# MAIN.net
KiCad netlist of a schematic drawn in Altium Designer
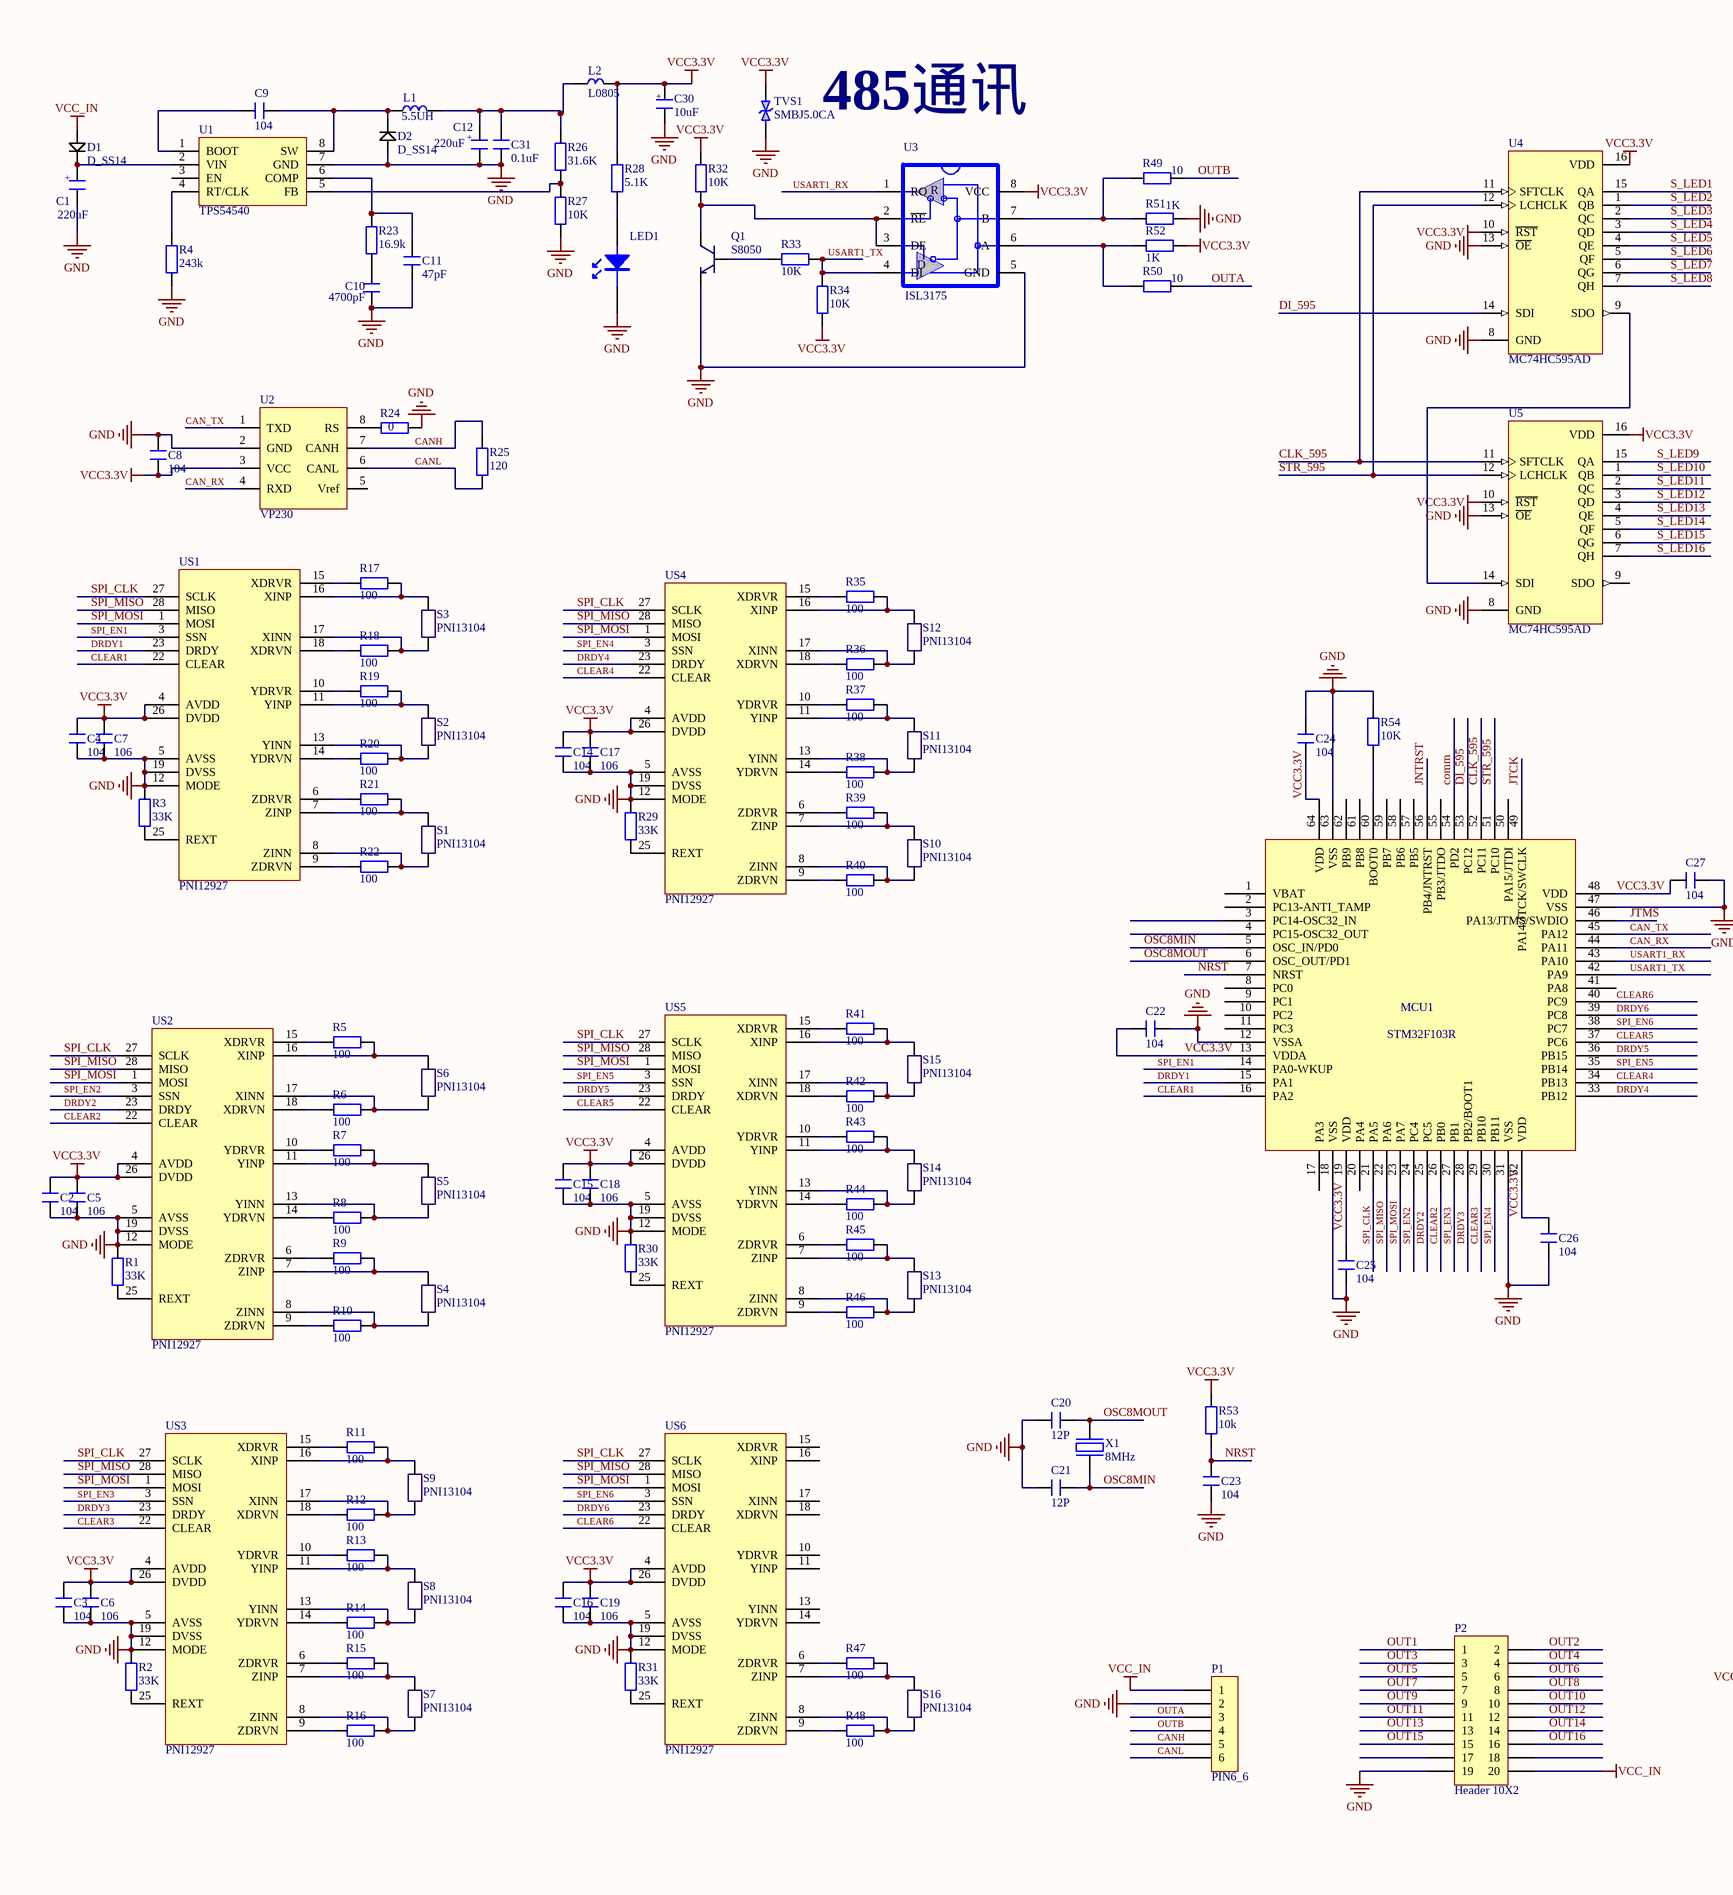
[diagram p0: MAIN.SchDoc, left]
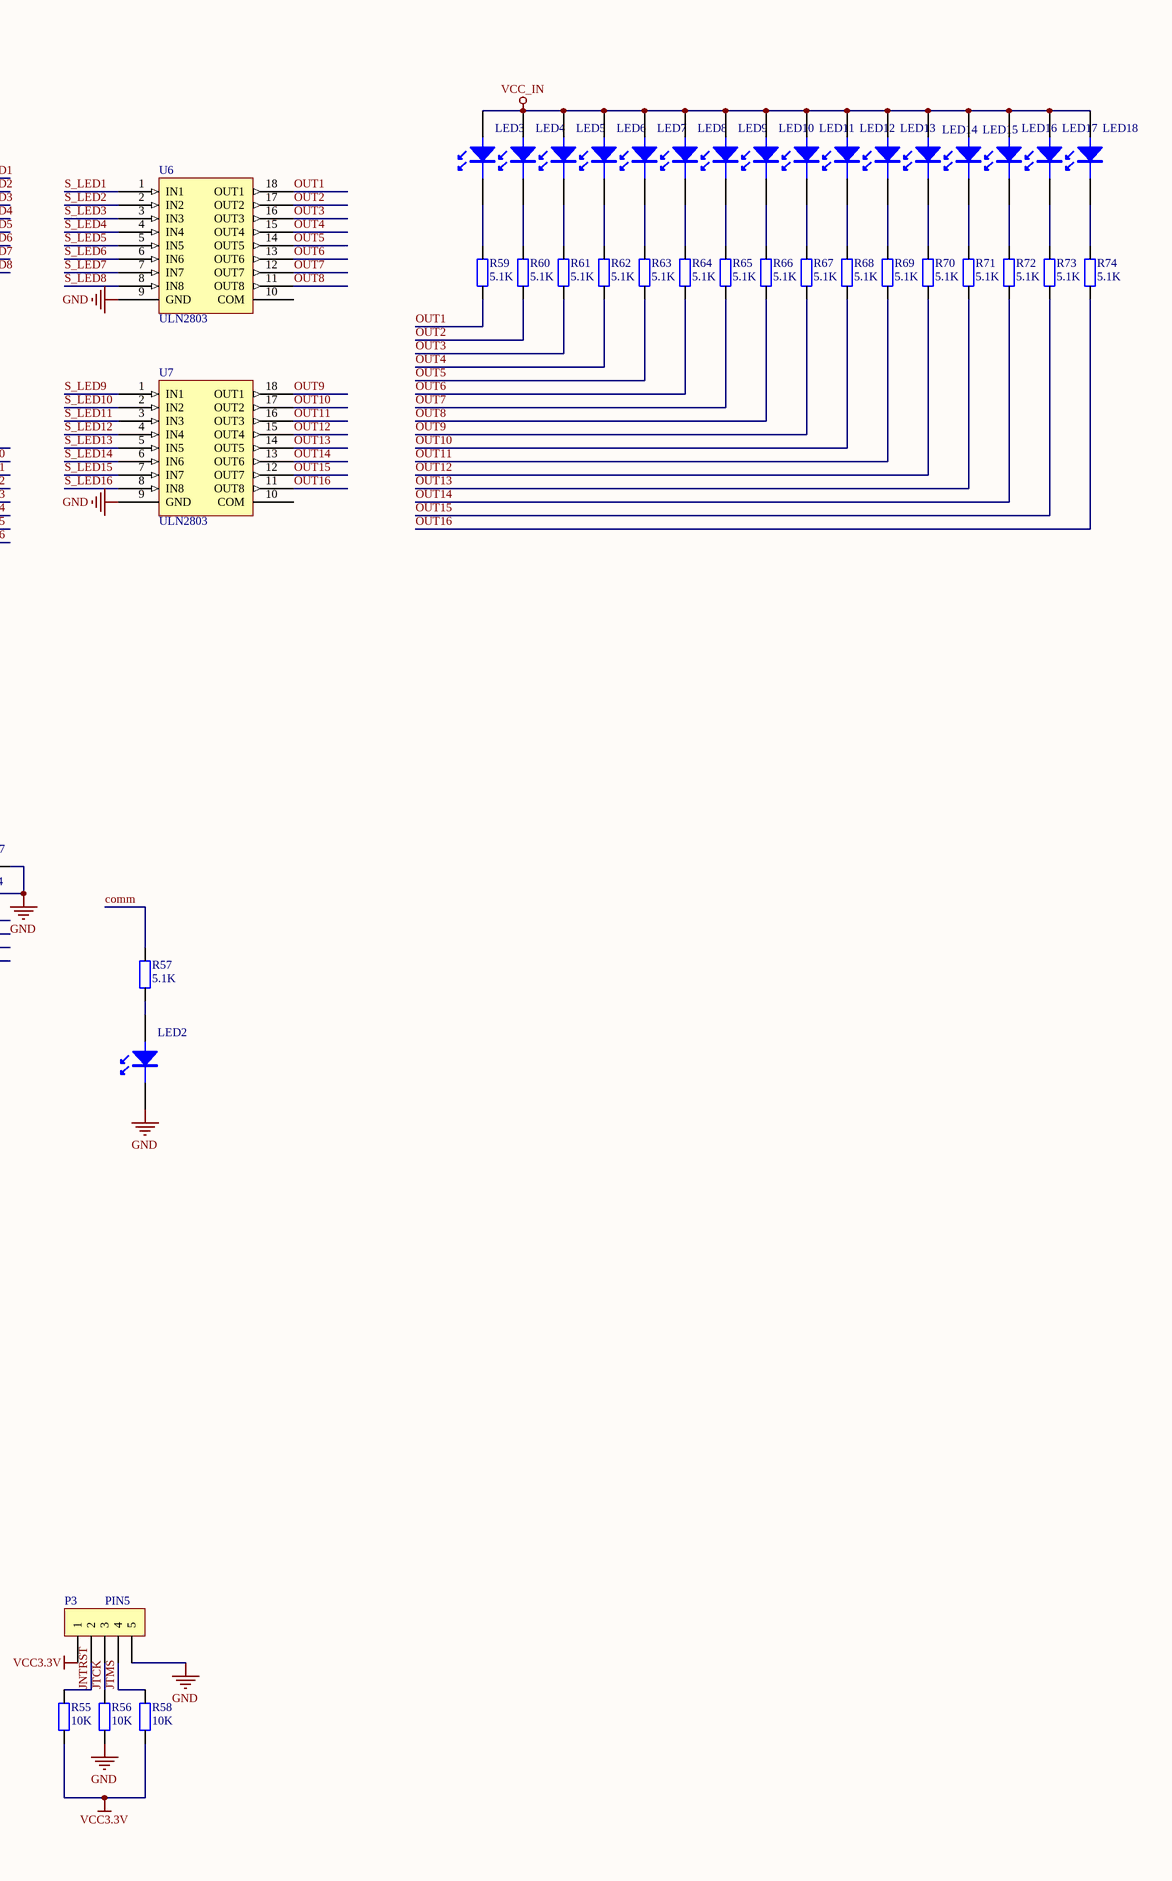
[diagram p1: MAIN.SchDoc, right]

(export (version "E")
  (design (tool "Eeschema 10.0.6"))
  (components
    (comp (ref "C1")
      (value "220uF")
      (footprint "自编封装库:CAP_SMT_1")
      (libsource (lib "自编原件库") (part "CAP_SMT_1"))
    )
    (comp (ref "C2") (value "104") (footprint "自编封装库:C0603") (libsource (lib "自编原件库") (part "CAP_SMT_0603")))
    (comp (ref "C3") (value "104") (footprint "自编封装库:C0603") (libsource (lib "自编原件库") (part "CAP_SMT_0603")))
    (comp (ref "C4") (value "104") (footprint "自编封装库:C0603") (libsource (lib "自编原件库") (part "CAP_SMT_0603")))
    (comp (ref "C5") (value "106") (footprint "自编封装库:C0805") (libsource (lib "自编原件库") (part "CAP_SMT_0805")))
    (comp (ref "C6") (value "106") (footprint "自编封装库:C0805") (libsource (lib "自编原件库") (part "CAP_SMT_0805")))
    (comp (ref "C7") (value "106") (footprint "自编封装库:C0805") (libsource (lib "自编原件库") (part "CAP_SMT_0805")))
    (comp (ref "C8") (value "104") (footprint "自编封装库:C0603") (libsource (lib "自编原件库") (part "CAP_SMT_0603")))
    (comp (ref "C9") (value "104") (footprint "自编封装库:C0603") (libsource (lib "自编原件库") (part "CAP_SMT_0603")))
    (comp (ref "C10")
      (value "4700pF")
      (footprint "自编封装库:C0603")
      (libsource (lib "自编原件库") (part "CAP_SMT_0603"))
    )
    (comp (ref "C11")
      (value "47pF")
      (footprint "自编封装库:C0603")
      (libsource (lib "自编原件库") (part "CAP_SMT_0603"))
    )
    (comp (ref "C12")
      (value "220uF")
      (footprint "自编封装库:CAP_SMT_1")
      (libsource (lib "自编原件库") (part "CAP_SMT_1"))
    )
    (comp (ref "C14") (value "104") (footprint "自编封装库:C0603") (libsource (lib "自编原件库") (part "CAP_SMT_0603")))
    (comp (ref "C15") (value "104") (footprint "自编封装库:C0603") (libsource (lib "自编原件库") (part "CAP_SMT_0603")))
    (comp (ref "C16") (value "104") (footprint "自编封装库:C0603") (libsource (lib "自编原件库") (part "CAP_SMT_0603")))
    (comp (ref "C17") (value "106") (footprint "自编封装库:C0805") (libsource (lib "自编原件库") (part "CAP_SMT_0805")))
    (comp (ref "C18") (value "106") (footprint "自编封装库:C0805") (libsource (lib "自编原件库") (part "CAP_SMT_0805")))
    (comp (ref "C19") (value "106") (footprint "自编封装库:C0805") (libsource (lib "自编原件库") (part "CAP_SMT_0805")))
    (comp (ref "C20") (value "12P") (footprint "自编封装库:C0603") (libsource (lib "自编原件库") (part "CAP_SMT_0603")))
    (comp (ref "C21") (value "12P") (footprint "自编封装库:C0603") (libsource (lib "自编原件库") (part "CAP_SMT_0603")))
    (comp (ref "C22") (value "104") (footprint "自编封装库:C0603") (libsource (lib "自编原件库") (part "CAP_SMT_0603")))
    (comp (ref "C23") (value "104") (footprint "自编封装库:C0603") (libsource (lib "自编原件库") (part "CAP_SMT_0603")))
    (comp (ref "C24") (value "104") (footprint "自编封装库:C0603") (libsource (lib "自编原件库") (part "CAP_SMT_0603")))
    (comp (ref "C25") (value "104") (footprint "自编封装库:C0603") (libsource (lib "自编原件库") (part "CAP_SMT_0603")))
    (comp (ref "C26") (value "104") (footprint "自编封装库:C0603") (libsource (lib "自编原件库") (part "CAP_SMT_0603")))
    (comp (ref "C27") (value "104") (footprint "自编封装库:C0603") (libsource (lib "自编原件库") (part "CAP_SMT_0603")))
    (comp (ref "C30")
      (value "10uF")
      (footprint "自编封装库:C1206")
      (libsource (lib "自编原件库") (part "CAP_SMT_1206"))
    )
    (comp (ref "C31")
      (value "0.1uF")
      (footprint "自编封装库:C0603")
      (libsource (lib "自编原件库") (part "CAP_SMT_0603"))
    )
    (comp (ref "D1") (value "D_SS14") (footprint "自编封装库:D_3.0*5.0") (libsource (lib "自编原件库") (part "D_SS14")))
    (comp (ref "D2") (value "D_SS14") (footprint "自编封装库:D_3.0*5.0") (libsource (lib "自编原件库") (part "D_SS14")))
    (comp (ref "L1") (value "5.5UH") (footprint "自编封装库:L7*7") (libsource (lib "自编原件库") (part "L_SMT_7*7*4")))
    (comp (ref "L2") (value "L0805") (footprint "自编封装库:L0805") (libsource (lib "自编原件库") (part "L_SMT_0805")))
    (comp (ref "LED1") (value "~") (footprint "LED1-AK") (libsource (lib "*") (part "LED")))
    (comp (ref "LED2") (value "~") (footprint "LED1-AK") (libsource (lib "*") (part "LED")))
    (comp (ref "LED3") (value "~") (footprint "LED1-AK") (libsource (lib "*") (part "LED")))
    (comp (ref "LED4") (value "~") (footprint "LED1-AK") (libsource (lib "*") (part "LED")))
    (comp (ref "LED5") (value "~") (footprint "LED1-AK") (libsource (lib "*") (part "LED")))
    (comp (ref "LED6") (value "~") (footprint "LED1-AK") (libsource (lib "*") (part "LED")))
    (comp (ref "LED7") (value "~") (footprint "LED1-AK") (libsource (lib "*") (part "LED")))
    (comp (ref "LED8") (value "~") (footprint "LED1-AK") (libsource (lib "*") (part "LED")))
    (comp (ref "LED9") (value "~") (footprint "LED1-AK") (libsource (lib "*") (part "LED")))
    (comp (ref "LED10") (value "~") (footprint "LED1-AK") (libsource (lib "*") (part "LED")))
    (comp (ref "LED11") (value "~") (footprint "LED1-AK") (libsource (lib "*") (part "LED")))
    (comp (ref "LED12") (value "~") (footprint "LED1-AK") (libsource (lib "*") (part "LED")))
    (comp (ref "LED13") (value "~") (footprint "LED1-AK") (libsource (lib "*") (part "LED")))
    (comp (ref "LED14") (value "~") (footprint "LED1-AK") (libsource (lib "*") (part "LED")))
    (comp (ref "LED15") (value "~") (footprint "LED1-AK") (libsource (lib "*") (part "LED")))
    (comp (ref "LED16") (value "~") (footprint "LED1-AK") (libsource (lib "*") (part "LED")))
    (comp (ref "LED17") (value "~") (footprint "LED1-AK") (libsource (lib "*") (part "LED")))
    (comp (ref "LED18") (value "~") (footprint "LED1-AK") (libsource (lib "*") (part "LED")))
    (comp (ref "MCU1")
      (value "STM32F103R")
      (footprint "TQFP64_STM32")
      (libsource (lib "自编原件库") (part "STM32F103RXX_64"))
    )
    (comp (ref "P1")
      (value "PIN6_6")
      (footprint "自编封装库:KF350W_6")
      (libsource (lib "自编原件库") (part "PIN6_6*1_3.81MM"))
    )
    (comp (ref "P2")
      (value "Header 10X2")
      (footprint "PIN20_10*2_2.54MM_1")
      (description "Header, 10-Pin, Dual row")
      (fields (field (name "PUBLISHER") "Altium Limited"))
      (libsource (lib "Miscellaneous Connectors") (part "Header 10X2"))
    )
    (comp (ref "P3")
      (value "PIN5")
      (footprint "自编封装库:PIN5_5*1_2.54MM_2")
      (libsource (lib "自编原件库") (part "PIN5_5*1_2.54mm"))
    )
    (comp (ref "Q1") (value "S8050") (footprint "自编封装库:SOT-23") (libsource (lib "自编原件库") (part "QS8050")))
    (comp (ref "R1") (value "33K") (footprint "R0603") (libsource (lib "自编原件库") (part "RES_SMT_0603")))
    (comp (ref "R2") (value "33K") (footprint "R0603") (libsource (lib "自编原件库") (part "RES_SMT_0603")))
    (comp (ref "R3") (value "33K") (footprint "R0603") (libsource (lib "自编原件库") (part "RES_SMT_0603")))
    (comp (ref "R4") (value "243k") (footprint "R0603") (libsource (lib "自编原件库") (part "RES_SMT_0603")))
    (comp (ref "R5") (value "100") (footprint "R0603") (libsource (lib "自编原件库") (part "RES_SMT_0603")))
    (comp (ref "R6") (value "100") (footprint "R0603") (libsource (lib "自编原件库") (part "RES_SMT_0603")))
    (comp (ref "R7") (value "100") (footprint "R0603") (libsource (lib "自编原件库") (part "RES_SMT_0603")))
    (comp (ref "R8") (value "100") (footprint "R0603") (libsource (lib "自编原件库") (part "RES_SMT_0603")))
    (comp (ref "R9") (value "100") (footprint "R0603") (libsource (lib "自编原件库") (part "RES_SMT_0603")))
    (comp (ref "R10") (value "100") (footprint "R0603") (libsource (lib "自编原件库") (part "RES_SMT_0603")))
    (comp (ref "R11") (value "100") (footprint "R0603") (libsource (lib "自编原件库") (part "RES_SMT_0603")))
    (comp (ref "R12") (value "100") (footprint "R0603") (libsource (lib "自编原件库") (part "RES_SMT_0603")))
    (comp (ref "R13") (value "100") (footprint "R0603") (libsource (lib "自编原件库") (part "RES_SMT_0603")))
    (comp (ref "R14") (value "100") (footprint "R0603") (libsource (lib "自编原件库") (part "RES_SMT_0603")))
    (comp (ref "R15") (value "100") (footprint "R0603") (libsource (lib "自编原件库") (part "RES_SMT_0603")))
    (comp (ref "R16") (value "100") (footprint "R0603") (libsource (lib "自编原件库") (part "RES_SMT_0603")))
    (comp (ref "R17") (value "100") (footprint "R0603") (libsource (lib "自编原件库") (part "RES_SMT_0603")))
    (comp (ref "R18") (value "100") (footprint "R0603") (libsource (lib "自编原件库") (part "RES_SMT_0603")))
    (comp (ref "R19") (value "100") (footprint "R0603") (libsource (lib "自编原件库") (part "RES_SMT_0603")))
    (comp (ref "R20") (value "100") (footprint "R0603") (libsource (lib "自编原件库") (part "RES_SMT_0603")))
    (comp (ref "R21") (value "100") (footprint "R0603") (libsource (lib "自编原件库") (part "RES_SMT_0603")))
    (comp (ref "R22") (value "100") (footprint "R0603") (libsource (lib "自编原件库") (part "RES_SMT_0603")))
    (comp (ref "R23") (value "16.9k") (footprint "R0603") (libsource (lib "自编原件库") (part "RES_SMT_0603")))
    (comp (ref "R24") (value "0") (footprint "R0603") (libsource (lib "自编原件库") (part "RES_SMT_0603")))
    (comp (ref "R25") (value "120") (footprint "R0603") (libsource (lib "自编原件库") (part "RES_SMT_0603")))
    (comp (ref "R26") (value "31.6K") (footprint "R0603") (libsource (lib "自编原件库") (part "RES_SMT_0603")))
    (comp (ref "R27") (value "10K") (footprint "R0603") (libsource (lib "自编原件库") (part "RES_SMT_0603")))
    (comp (ref "R28") (value "5.1K") (footprint "R0603") (libsource (lib "自编原件库") (part "RES_SMT_0603")))
    (comp (ref "R29") (value "33K") (footprint "R0603") (libsource (lib "自编原件库") (part "RES_SMT_0603")))
    (comp (ref "R30") (value "33K") (footprint "R0603") (libsource (lib "自编原件库") (part "RES_SMT_0603")))
    (comp (ref "R31") (value "33K") (footprint "R0603") (libsource (lib "自编原件库") (part "RES_SMT_0603")))
    (comp (ref "R32") (value "10K") (footprint "R0603") (libsource (lib "自编原件库") (part "RES_SMT_0603")))
    (comp (ref "R33") (value "10K") (footprint "R0603") (libsource (lib "自编原件库") (part "RES_SMT_0603")))
    (comp (ref "R34") (value "10K") (footprint "R0603") (libsource (lib "自编原件库") (part "RES_SMT_0603")))
    (comp (ref "R35") (value "100") (footprint "R0603") (libsource (lib "自编原件库") (part "RES_SMT_0603")))
    (comp (ref "R36") (value "100") (footprint "R0603") (libsource (lib "自编原件库") (part "RES_SMT_0603")))
    (comp (ref "R37") (value "100") (footprint "R0603") (libsource (lib "自编原件库") (part "RES_SMT_0603")))
    (comp (ref "R38") (value "100") (footprint "R0603") (libsource (lib "自编原件库") (part "RES_SMT_0603")))
    (comp (ref "R39") (value "100") (footprint "R0603") (libsource (lib "自编原件库") (part "RES_SMT_0603")))
    (comp (ref "R40") (value "100") (footprint "R0603") (libsource (lib "自编原件库") (part "RES_SMT_0603")))
    (comp (ref "R41") (value "100") (footprint "R0603") (libsource (lib "自编原件库") (part "RES_SMT_0603")))
    (comp (ref "R42") (value "100") (footprint "R0603") (libsource (lib "自编原件库") (part "RES_SMT_0603")))
    (comp (ref "R43") (value "100") (footprint "R0603") (libsource (lib "自编原件库") (part "RES_SMT_0603")))
    (comp (ref "R44") (value "100") (footprint "R0603") (libsource (lib "自编原件库") (part "RES_SMT_0603")))
    (comp (ref "R45") (value "100") (footprint "R0603") (libsource (lib "自编原件库") (part "RES_SMT_0603")))
    (comp (ref "R46") (value "100") (footprint "R0603") (libsource (lib "自编原件库") (part "RES_SMT_0603")))
    (comp (ref "R47") (value "100") (footprint "R0603") (libsource (lib "自编原件库") (part "RES_SMT_0603")))
    (comp (ref "R48") (value "100") (footprint "R0603") (libsource (lib "自编原件库") (part "RES_SMT_0603")))
    (comp (ref "R49") (value "10") (footprint "R0603") (libsource (lib "自编原件库") (part "RES_SMT_0603")))
    (comp (ref "R50") (value "10") (footprint "R0603") (libsource (lib "自编原件库") (part "RES_SMT_0603")))
    (comp (ref "R51") (value "1K") (footprint "R0603") (libsource (lib "自编原件库") (part "RES_SMT_0603")))
    (comp (ref "R52") (value "1K") (footprint "R0603") (libsource (lib "自编原件库") (part "RES_SMT_0603")))
    (comp (ref "R53") (value "10k") (footprint "R0603") (libsource (lib "自编原件库") (part "RES_SMT_0603")))
    (comp (ref "R54") (value "10K") (footprint "R0603") (libsource (lib "自编原件库") (part "RES_SMT_0603")))
    (comp (ref "R55") (value "10K") (footprint "R0603") (libsource (lib "自编原件库") (part "RES_SMT_0603")))
    (comp (ref "R56") (value "10K") (footprint "R0603") (libsource (lib "自编原件库") (part "RES_SMT_0603")))
    (comp (ref "R57") (value "5.1K") (footprint "R0603") (libsource (lib "自编原件库") (part "RES_SMT_0603")))
    (comp (ref "R58") (value "10K") (footprint "R0603") (libsource (lib "自编原件库") (part "RES_SMT_0603")))
    (comp (ref "R59") (value "5.1K") (footprint "R0603") (libsource (lib "自编原件库") (part "RES_SMT_0603")))
    (comp (ref "R60") (value "5.1K") (footprint "R0603") (libsource (lib "自编原件库") (part "RES_SMT_0603")))
    (comp (ref "R61") (value "5.1K") (footprint "R0603") (libsource (lib "自编原件库") (part "RES_SMT_0603")))
    (comp (ref "R62") (value "5.1K") (footprint "R0603") (libsource (lib "自编原件库") (part "RES_SMT_0603")))
    (comp (ref "R63") (value "5.1K") (footprint "R0603") (libsource (lib "自编原件库") (part "RES_SMT_0603")))
    (comp (ref "R64") (value "5.1K") (footprint "R0603") (libsource (lib "自编原件库") (part "RES_SMT_0603")))
    (comp (ref "R65") (value "5.1K") (footprint "R0603") (libsource (lib "自编原件库") (part "RES_SMT_0603")))
    (comp (ref "R66") (value "5.1K") (footprint "R0603") (libsource (lib "自编原件库") (part "RES_SMT_0603")))
    (comp (ref "R67") (value "5.1K") (footprint "R0603") (libsource (lib "自编原件库") (part "RES_SMT_0603")))
    (comp (ref "R68") (value "5.1K") (footprint "R0603") (libsource (lib "自编原件库") (part "RES_SMT_0603")))
    (comp (ref "R69") (value "5.1K") (footprint "R0603") (libsource (lib "自编原件库") (part "RES_SMT_0603")))
    (comp (ref "R70") (value "5.1K") (footprint "R0603") (libsource (lib "自编原件库") (part "RES_SMT_0603")))
    (comp (ref "R71") (value "5.1K") (footprint "R0603") (libsource (lib "自编原件库") (part "RES_SMT_0603")))
    (comp (ref "R72") (value "5.1K") (footprint "R0603") (libsource (lib "自编原件库") (part "RES_SMT_0603")))
    (comp (ref "R73") (value "5.1K") (footprint "R0603") (libsource (lib "自编原件库") (part "RES_SMT_0603")))
    (comp (ref "R74") (value "5.1K") (footprint "R0603") (libsource (lib "自编原件库") (part "RES_SMT_0603")))
    (comp (ref "S1")
      (value "PNI13104")
      (footprint "自编封装库:PNI-13104")
      (libsource (lib "自编原件库") (part "PNI13104"))
    )
    (comp (ref "S2")
      (value "PNI13104")
      (footprint "自编封装库:PNI-13104")
      (libsource (lib "自编原件库") (part "PNI13104"))
    )
    (comp (ref "S3")
      (value "PNI13104")
      (footprint "自编封装库:PNI-13104")
      (libsource (lib "自编原件库") (part "PNI13104"))
    )
    (comp (ref "S4")
      (value "PNI13104")
      (footprint "自编封装库:PNI-13104")
      (libsource (lib "自编原件库") (part "PNI13104"))
    )
    (comp (ref "S5")
      (value "PNI13104")
      (footprint "自编封装库:PNI-13104")
      (libsource (lib "自编原件库") (part "PNI13104"))
    )
    (comp (ref "S6")
      (value "PNI13104")
      (footprint "自编封装库:PNI-13104")
      (libsource (lib "自编原件库") (part "PNI13104"))
    )
    (comp (ref "S7")
      (value "PNI13104")
      (footprint "自编封装库:PNI-13104")
      (libsource (lib "自编原件库") (part "PNI13104"))
    )
    (comp (ref "S8")
      (value "PNI13104")
      (footprint "自编封装库:PNI-13104")
      (libsource (lib "自编原件库") (part "PNI13104"))
    )
    (comp (ref "S9")
      (value "PNI13104")
      (footprint "自编封装库:PNI-13104")
      (libsource (lib "自编原件库") (part "PNI13104"))
    )
    (comp (ref "S10")
      (value "PNI13104")
      (footprint "自编封装库:PNI-13104")
      (libsource (lib "自编原件库") (part "PNI13104"))
    )
    (comp (ref "S11")
      (value "PNI13104")
      (footprint "自编封装库:PNI-13104")
      (libsource (lib "自编原件库") (part "PNI13104"))
    )
    (comp (ref "S12")
      (value "PNI13104")
      (footprint "自编封装库:PNI-13104")
      (libsource (lib "自编原件库") (part "PNI13104"))
    )
    (comp (ref "S13")
      (value "PNI13104")
      (footprint "自编封装库:PNI-13104")
      (libsource (lib "自编原件库") (part "PNI13104"))
    )
    (comp (ref "S14")
      (value "PNI13104")
      (footprint "自编封装库:PNI-13104")
      (libsource (lib "自编原件库") (part "PNI13104"))
    )
    (comp (ref "S15")
      (value "PNI13104")
      (footprint "自编封装库:PNI-13104")
      (libsource (lib "自编原件库") (part "PNI13104"))
    )
    (comp (ref "S16")
      (value "PNI13104")
      (footprint "自编封装库:PNI-13104")
      (libsource (lib "自编原件库") (part "PNI13104"))
    )
    (comp (ref "TVS1")
      (value "SMBJ5.0CA")
      (footprint "SMBJ6.5CA")
      (description "片式瞬态抑制二极管")
      (libsource (lib "自编原件库") (part "TVS"))
    )
    (comp (ref "U1")
      (value "TPS54540")
      (footprint "自编封装库:SOP8_1")
      (libsource (lib "自编原件库") (part "TPS54540"))
    )
    (comp (ref "U2") (value "VP230") (footprint "自编封装库:SOP8") (libsource (lib "自编原件库") (part "VP230")))
    (comp (ref "U3") (value "ISL3175") (footprint "SO-8") (libsource (lib "*") (part "MAX485")))
    (comp (ref "U4")
      (value "MC74HC595AD")
      (footprint "自编封装库:SOP16")
      (description "8-Bit Serial-Input/Serial or Prallel-Output Shift Register with Latched 3-State Outputs")
      (fields (field (name "PUBLISHER") "Altium Limited"))
      (libsource (lib "ON Semi Logic Register") (part "MC74HC595AD"))
    )
    (comp (ref "U5")
      (value "MC74HC595AD")
      (footprint "sop16")
      (description "8-Bit Serial-Input/Serial or Prallel-Output Shift Register with Latched 3-State Outputs")
      (fields (field (name "PUBLISHER") "Altium Limited"))
      (libsource (lib "ON Semi Logic Register") (part "MC74HC595AD"))
    )
    (comp (ref "U6") (value "ULN2803") (footprint "SO-G18") (libsource (lib "总图") (part "ULN2803")))
    (comp (ref "U7") (value "ULN2803") (footprint "SO-G18") (libsource (lib "总图") (part "ULN2803")))
    (comp (ref "US1")
      (value "PNI12927")
      (footprint "自编封装库:MLF_28")
      (libsource (lib "自编原件库") (part "PNI12927"))
    )
    (comp (ref "US2")
      (value "PNI12927")
      (footprint "自编封装库:MLF_28")
      (libsource (lib "自编原件库") (part "PNI12927"))
    )
    (comp (ref "US3")
      (value "PNI12927")
      (footprint "自编封装库:MLF_28")
      (libsource (lib "自编原件库") (part "PNI12927"))
    )
    (comp (ref "US4")
      (value "PNI12927")
      (footprint "自编封装库:MLF_28")
      (libsource (lib "自编原件库") (part "PNI12927"))
    )
    (comp (ref "US5")
      (value "PNI12927")
      (footprint "自编封装库:MLF_28")
      (libsource (lib "自编原件库") (part "PNI12927"))
    )
    (comp (ref "US6")
      (value "PNI12927")
      (footprint "自编封装库:MLF_28")
      (libsource (lib "自编原件库") (part "PNI12927"))
    )
    (comp (ref "X1")
      (value "8MHz")
      (footprint "自编封装库:XTAL_49SMD")
      (description "假贴片晶振")
      (libsource (lib "自编原件库") (part "XTAL_49SMD"))
    )
  )
  (nets
    (net (code "1") (name "/CANH") (class "Default")
      (node (ref "P1") (pin "5") (pinfunction "5_5") (pintype "passive"))
      (node (ref "R25") (pin "2") (pinfunction "2_2") (pintype "passive"))
      (node (ref "U2") (pin "7") (pinfunction "CANH_7") (pintype "passive"))
    )
    (net (code "2") (name "/CANL") (class "Default")
      (node (ref "P1") (pin "6") (pinfunction "6_6") (pintype "passive"))
      (node (ref "R25") (pin "1") (pinfunction "1_1") (pintype "passive"))
      (node (ref "U2") (pin "6") (pinfunction "CANL_6") (pintype "passive"))
    )
    (net (code "3") (name "/CAN_RX") (class "Default")
      (node (ref "MCU1") (pin "44") (pinfunction "PA11_44") (pintype "passive"))
      (node (ref "U2") (pin "4") (pinfunction "RXD_4") (pintype "passive"))
    )
    (net (code "4") (name "/CAN_TX") (class "Default")
      (node (ref "MCU1") (pin "45") (pinfunction "PA12_45") (pintype "passive"))
      (node (ref "U2") (pin "1") (pinfunction "TXD_1") (pintype "passive"))
    )
    (net (code "5") (name "/CLEAR1") (class "Default")
      (node (ref "MCU1") (pin "16") (pinfunction "PA2_16") (pintype "passive"))
      (node (ref "US1") (pin "22") (pinfunction "CLEAR_22") (pintype "passive"))
    )
    (net (code "6") (name "/CLEAR2") (class "Default")
      (node (ref "MCU1") (pin "26") (pinfunction "PB0_26") (pintype "passive"))
      (node (ref "US2") (pin "22") (pinfunction "CLEAR_22") (pintype "passive"))
    )
    (net (code "7") (name "/CLEAR3") (class "Default")
      (node (ref "MCU1") (pin "29") (pinfunction "PB10_29") (pintype "passive"))
      (node (ref "US3") (pin "22") (pinfunction "CLEAR_22") (pintype "passive"))
    )
    (net (code "8") (name "/CLEAR4") (class "Default")
      (node (ref "MCU1") (pin "34") (pinfunction "PB13_34") (pintype "passive"))
      (node (ref "US4") (pin "22") (pinfunction "CLEAR_22") (pintype "passive"))
    )
    (net (code "9") (name "/CLEAR5") (class "Default")
      (node (ref "MCU1") (pin "37") (pinfunction "PC6_37") (pintype "passive"))
      (node (ref "US5") (pin "22") (pinfunction "CLEAR_22") (pintype "passive"))
    )
    (net (code "10") (name "/CLEAR6") (class "Default")
      (node (ref "MCU1") (pin "40") (pinfunction "PC9_40") (pintype "passive"))
      (node (ref "US6") (pin "22") (pinfunction "CLEAR_22") (pintype "passive"))
    )
    (net (code "11") (name "/CLK_595") (class "Default")
      (node (ref "MCU1") (pin "52") (pinfunction "PC11_52") (pintype "passive"))
      (node (ref "U4") (pin "11") (pinfunction "SFTCLK_11") (pintype "input"))
      (node (ref "U5") (pin "11") (pinfunction "SFTCLK_11") (pintype "input"))
    )
    (net (code "12") (name "/DI_595") (class "Default")
      (node (ref "MCU1") (pin "53") (pinfunction "PC12_53") (pintype "passive"))
      (node (ref "U4") (pin "14") (pinfunction "SDI_14") (pintype "input"))
    )
    (net (code "13") (name "/DRDY1") (class "Default")
      (node (ref "MCU1") (pin "15") (pinfunction "PA1_15") (pintype "passive"))
      (node (ref "US1") (pin "23") (pinfunction "DRDY_23") (pintype "passive"))
    )
    (net (code "14") (name "/DRDY2") (class "Default")
      (node (ref "MCU1") (pin "25") (pinfunction "PC5_25") (pintype "passive"))
      (node (ref "US2") (pin "23") (pinfunction "DRDY_23") (pintype "passive"))
    )
    (net (code "15") (name "/DRDY3") (class "Default")
      (node (ref "MCU1") (pin "28") (pinfunction "PB2/BOOT1_28") (pintype "passive"))
      (node (ref "US3") (pin "23") (pinfunction "DRDY_23") (pintype "passive"))
    )
    (net (code "16") (name "/DRDY4") (class "Default")
      (node (ref "MCU1") (pin "33") (pinfunction "PB12_33") (pintype "passive"))
      (node (ref "US4") (pin "23") (pinfunction "DRDY_23") (pintype "passive"))
    )
    (net (code "17") (name "/DRDY5") (class "Default")
      (node (ref "MCU1") (pin "36") (pinfunction "PB15_36") (pintype "passive"))
      (node (ref "US5") (pin "23") (pinfunction "DRDY_23") (pintype "passive"))
    )
    (net (code "18") (name "/DRDY6") (class "Default")
      (node (ref "MCU1") (pin "39") (pinfunction "PC8_39") (pintype "passive"))
      (node (ref "US6") (pin "23") (pinfunction "DRDY_23") (pintype "passive"))
    )
    (net (code "19") (name "/JNTRST") (class "Default")
      (node (ref "MCU1") (pin "56") (pinfunction "PB4/JNTRST_56") (pintype "passive"))
      (node (ref "P3") (pin "2") (pinfunction "2_2") (pintype "passive"))
      (node (ref "R55") (pin "2") (pinfunction "2_2") (pintype "passive"))
    )
    (net (code "20") (name "/JTCK") (class "Default")
      (node (ref "MCU1") (pin "49") (pinfunction "PA14/JTCK/SWCLK_49") (pintype "passive"))
      (node (ref "P3") (pin "3") (pinfunction "3_3") (pintype "passive"))
      (node (ref "R56") (pin "2") (pinfunction "2_2") (pintype "passive"))
    )
    (net (code "21") (name "/JTMS") (class "Default")
      (node (ref "MCU1") (pin "46") (pinfunction "PA13/JTMS/SWDIO_46") (pintype "passive"))
      (node (ref "P3") (pin "4") (pinfunction "4_4") (pintype "passive"))
      (node (ref "R58") (pin "2") (pinfunction "2_2") (pintype "passive"))
    )
    (net (code "22") (name "/NRST") (class "Default")
      (node (ref "C23") (pin "2") (pinfunction "2_2") (pintype "passive"))
      (node (ref "MCU1") (pin "7") (pinfunction "NRST_7") (pintype "passive"))
      (node (ref "R53") (pin "1") (pinfunction "1_1") (pintype "passive"))
    )
    (net (code "23") (name "/OSC8MIN") (class "Default")
      (node (ref "C21") (pin "2") (pinfunction "2_2") (pintype "passive"))
      (node (ref "MCU1") (pin "5") (pinfunction "OSC_IN/PD0_5") (pintype "passive"))
      (node (ref "X1") (pin "1") (pinfunction "1_1") (pintype "passive"))
    )
    (net (code "24") (name "/OSC8MOUT") (class "Default")
      (node (ref "C20") (pin "2") (pinfunction "2_2") (pintype "passive"))
      (node (ref "MCU1") (pin "6") (pinfunction "OSC_OUT/PD1_6") (pintype "passive"))
      (node (ref "X1") (pin "2") (pinfunction "2_2") (pintype "passive"))
    )
    (net (code "25") (name "/OUT1") (class "Default")
      (node (ref "P2") (pin "1") (pinfunction "1_1") (pintype "passive"))
      (node (ref "R59") (pin "1") (pinfunction "1_1") (pintype "passive"))
      (node (ref "U6") (pin "18") (pinfunction "OUT1_18") (pintype "output"))
    )
    (net (code "26") (name "/OUT2") (class "Default")
      (node (ref "P2") (pin "2") (pinfunction "2_2") (pintype "passive"))
      (node (ref "R60") (pin "1") (pinfunction "1_1") (pintype "passive"))
      (node (ref "U6") (pin "17") (pinfunction "OUT2_17") (pintype "output"))
    )
    (net (code "27") (name "/OUT3") (class "Default")
      (node (ref "P2") (pin "3") (pinfunction "3_3") (pintype "passive"))
      (node (ref "R61") (pin "1") (pinfunction "1_1") (pintype "passive"))
      (node (ref "U6") (pin "16") (pinfunction "OUT3_16") (pintype "output"))
    )
    (net (code "28") (name "/OUT4") (class "Default")
      (node (ref "P2") (pin "4") (pinfunction "4_4") (pintype "passive"))
      (node (ref "R62") (pin "1") (pinfunction "1_1") (pintype "passive"))
      (node (ref "U6") (pin "15") (pinfunction "OUT4_15") (pintype "output"))
    )
    (net (code "29") (name "/OUT5") (class "Default")
      (node (ref "P2") (pin "5") (pinfunction "5_5") (pintype "passive"))
      (node (ref "R63") (pin "1") (pinfunction "1_1") (pintype "passive"))
      (node (ref "U6") (pin "14") (pinfunction "OUT5_14") (pintype "output"))
    )
    (net (code "30") (name "/OUT6") (class "Default")
      (node (ref "P2") (pin "6") (pinfunction "6_6") (pintype "passive"))
      (node (ref "R64") (pin "1") (pinfunction "1_1") (pintype "passive"))
      (node (ref "U6") (pin "13") (pinfunction "OUT6_13") (pintype "output"))
    )
    (net (code "31") (name "/OUT7") (class "Default")
      (node (ref "P2") (pin "7") (pinfunction "7_7") (pintype "passive"))
      (node (ref "R65") (pin "1") (pinfunction "1_1") (pintype "passive"))
      (node (ref "U6") (pin "12") (pinfunction "OUT7_12") (pintype "output"))
    )
    (net (code "32") (name "/OUT8") (class "Default")
      (node (ref "P2") (pin "8") (pinfunction "8_8") (pintype "passive"))
      (node (ref "R66") (pin "1") (pinfunction "1_1") (pintype "passive"))
      (node (ref "U6") (pin "11") (pinfunction "OUT8_11") (pintype "output"))
    )
    (net (code "33") (name "/OUT9") (class "Default")
      (node (ref "P2") (pin "9") (pinfunction "9_9") (pintype "passive"))
      (node (ref "R67") (pin "1") (pinfunction "1_1") (pintype "passive"))
      (node (ref "U7") (pin "18") (pinfunction "OUT1_18") (pintype "output"))
    )
    (net (code "34") (name "/OUT10") (class "Default")
      (node (ref "P2") (pin "10") (pinfunction "10_10") (pintype "passive"))
      (node (ref "R68") (pin "1") (pinfunction "1_1") (pintype "passive"))
      (node (ref "U7") (pin "17") (pinfunction "OUT2_17") (pintype "output"))
    )
    (net (code "35") (name "/OUT11") (class "Default")
      (node (ref "P2") (pin "11") (pinfunction "11_11") (pintype "passive"))
      (node (ref "R69") (pin "1") (pinfunction "1_1") (pintype "passive"))
      (node (ref "U7") (pin "16") (pinfunction "OUT3_16") (pintype "output"))
    )
    (net (code "36") (name "/OUT12") (class "Default")
      (node (ref "P2") (pin "12") (pinfunction "12_12") (pintype "passive"))
      (node (ref "R70") (pin "1") (pinfunction "1_1") (pintype "passive"))
      (node (ref "U7") (pin "15") (pinfunction "OUT4_15") (pintype "output"))
    )
    (net (code "37") (name "/OUT13") (class "Default")
      (node (ref "P2") (pin "13") (pinfunction "13_13") (pintype "passive"))
      (node (ref "R71") (pin "1") (pinfunction "1_1") (pintype "passive"))
      (node (ref "U7") (pin "14") (pinfunction "OUT5_14") (pintype "output"))
    )
    (net (code "38") (name "/OUT14") (class "Default")
      (node (ref "P2") (pin "14") (pinfunction "14_14") (pintype "passive"))
      (node (ref "R72") (pin "1") (pinfunction "1_1") (pintype "passive"))
      (node (ref "U7") (pin "13") (pinfunction "OUT6_13") (pintype "output"))
    )
    (net (code "39") (name "/OUT15") (class "Default")
      (node (ref "P2") (pin "15") (pinfunction "15_15") (pintype "passive"))
      (node (ref "R73") (pin "1") (pinfunction "1_1") (pintype "passive"))
      (node (ref "U7") (pin "12") (pinfunction "OUT7_12") (pintype "output"))
    )
    (net (code "40") (name "/OUT16") (class "Default")
      (node (ref "P2") (pin "16") (pinfunction "16_16") (pintype "passive"))
      (node (ref "R74") (pin "1") (pinfunction "1_1") (pintype "passive"))
      (node (ref "U7") (pin "11") (pinfunction "OUT8_11") (pintype "output"))
    )
    (net (code "41") (name "/OUTA") (class "Default")
      (node (ref "P1") (pin "3") (pinfunction "3_3") (pintype "passive"))
      (node (ref "R50") (pin "1") (pinfunction "1_1") (pintype "passive"))
    )
    (net (code "42") (name "/OUTB") (class "Default")
      (node (ref "P1") (pin "4") (pinfunction "4_4") (pintype "passive"))
      (node (ref "R49") (pin "1") (pinfunction "1_1") (pintype "passive"))
    )
    (net (code "43") (name "/SPI_CLK") (class "Default")
      (node (ref "MCU1") (pin "21") (pinfunction "PA5_21") (pintype "passive"))
      (node (ref "US1") (pin "27") (pinfunction "SCLK_27") (pintype "passive"))
      (node (ref "US2") (pin "27") (pinfunction "SCLK_27") (pintype "passive"))
      (node (ref "US3") (pin "27") (pinfunction "SCLK_27") (pintype "passive"))
      (node (ref "US4") (pin "27") (pinfunction "SCLK_27") (pintype "passive"))
      (node (ref "US5") (pin "27") (pinfunction "SCLK_27") (pintype "passive"))
      (node (ref "US6") (pin "27") (pinfunction "SCLK_27") (pintype "passive"))
    )
    (net (code "44") (name "/SPI_EN1") (class "Default")
      (node (ref "MCU1") (pin "14") (pinfunction "PA0-WKUP_14") (pintype "passive"))
      (node (ref "US1") (pin "3") (pinfunction "SSN_3") (pintype "passive"))
    )
    (net (code "45") (name "/SPI_EN2") (class "Default")
      (node (ref "MCU1") (pin "24") (pinfunction "PC4_24") (pintype "passive"))
      (node (ref "US2") (pin "3") (pinfunction "SSN_3") (pintype "passive"))
    )
    (net (code "46") (name "/SPI_EN3") (class "Default")
      (node (ref "MCU1") (pin "27") (pinfunction "PB1_27") (pintype "passive"))
      (node (ref "US3") (pin "3") (pinfunction "SSN_3") (pintype "passive"))
    )
    (net (code "47") (name "/SPI_EN4") (class "Default")
      (node (ref "MCU1") (pin "30") (pinfunction "PB11_30") (pintype "passive"))
      (node (ref "US4") (pin "3") (pinfunction "SSN_3") (pintype "passive"))
    )
    (net (code "48") (name "/SPI_EN5") (class "Default")
      (node (ref "MCU1") (pin "35") (pinfunction "PB14_35") (pintype "passive"))
      (node (ref "US5") (pin "3") (pinfunction "SSN_3") (pintype "passive"))
    )
    (net (code "49") (name "/SPI_EN6") (class "Default")
      (node (ref "MCU1") (pin "38") (pinfunction "PC7_38") (pintype "passive"))
      (node (ref "US6") (pin "3") (pinfunction "SSN_3") (pintype "passive"))
    )
    (net (code "50") (name "/SPI_MISO") (class "Default")
      (node (ref "MCU1") (pin "22") (pinfunction "PA6_22") (pintype "passive"))
      (node (ref "US1") (pin "28") (pinfunction "MISO_28") (pintype "passive"))
      (node (ref "US2") (pin "28") (pinfunction "MISO_28") (pintype "passive"))
      (node (ref "US3") (pin "28") (pinfunction "MISO_28") (pintype "passive"))
      (node (ref "US4") (pin "28") (pinfunction "MISO_28") (pintype "passive"))
      (node (ref "US5") (pin "28") (pinfunction "MISO_28") (pintype "passive"))
      (node (ref "US6") (pin "28") (pinfunction "MISO_28") (pintype "passive"))
    )
    (net (code "51") (name "/SPI_MOSI") (class "Default")
      (node (ref "MCU1") (pin "23") (pinfunction "PA7_23") (pintype "passive"))
      (node (ref "US1") (pin "1") (pinfunction "MOSI_1") (pintype "passive"))
      (node (ref "US2") (pin "1") (pinfunction "MOSI_1") (pintype "passive"))
      (node (ref "US3") (pin "1") (pinfunction "MOSI_1") (pintype "passive"))
      (node (ref "US4") (pin "1") (pinfunction "MOSI_1") (pintype "passive"))
      (node (ref "US5") (pin "1") (pinfunction "MOSI_1") (pintype "passive"))
      (node (ref "US6") (pin "1") (pinfunction "MOSI_1") (pintype "passive"))
    )
    (net (code "52") (name "/STR_595") (class "Default")
      (node (ref "MCU1") (pin "51") (pinfunction "PC10_51") (pintype "passive"))
      (node (ref "U4") (pin "12") (pinfunction "LCHCLK_12") (pintype "input"))
      (node (ref "U5") (pin "12") (pinfunction "LCHCLK_12") (pintype "input"))
    )
    (net (code "53") (name "/S_LED1") (class "Default")
      (node (ref "U4") (pin "15") (pinfunction "QA_15") (pintype "tri_state"))
      (node (ref "U6") (pin "1") (pinfunction "IN1_1") (pintype "input"))
    )
    (net (code "54") (name "/S_LED2") (class "Default")
      (node (ref "U4") (pin "1") (pinfunction "QB_1") (pintype "tri_state"))
      (node (ref "U6") (pin "2") (pinfunction "IN2_2") (pintype "input"))
    )
    (net (code "55") (name "/S_LED3") (class "Default")
      (node (ref "U4") (pin "2") (pinfunction "QC_2") (pintype "tri_state"))
      (node (ref "U6") (pin "3") (pinfunction "IN3_3") (pintype "input"))
    )
    (net (code "56") (name "/S_LED4") (class "Default")
      (node (ref "U4") (pin "3") (pinfunction "QD_3") (pintype "tri_state"))
      (node (ref "U6") (pin "4") (pinfunction "IN4_4") (pintype "input"))
    )
    (net (code "57") (name "/S_LED5") (class "Default")
      (node (ref "U4") (pin "4") (pinfunction "QE_4") (pintype "tri_state"))
      (node (ref "U6") (pin "5") (pinfunction "IN5_5") (pintype "input"))
    )
    (net (code "58") (name "/S_LED6") (class "Default")
      (node (ref "U4") (pin "5") (pinfunction "QF_5") (pintype "tri_state"))
      (node (ref "U6") (pin "6") (pinfunction "IN6_6") (pintype "input"))
    )
    (net (code "59") (name "/S_LED7") (class "Default")
      (node (ref "U4") (pin "6") (pinfunction "QG_6") (pintype "tri_state"))
      (node (ref "U6") (pin "7") (pinfunction "IN7_7") (pintype "input"))
    )
    (net (code "60") (name "/S_LED8") (class "Default")
      (node (ref "U4") (pin "7") (pinfunction "QH_7") (pintype "tri_state"))
      (node (ref "U6") (pin "8") (pinfunction "IN8_8") (pintype "input"))
    )
    (net (code "61") (name "/S_LED9") (class "Default")
      (node (ref "U5") (pin "15") (pinfunction "QA_15") (pintype "tri_state"))
      (node (ref "U7") (pin "1") (pinfunction "IN1_1") (pintype "input"))
    )
    (net (code "62") (name "/S_LED10") (class "Default")
      (node (ref "U5") (pin "1") (pinfunction "QB_1") (pintype "tri_state"))
      (node (ref "U7") (pin "2") (pinfunction "IN2_2") (pintype "input"))
    )
    (net (code "63") (name "/S_LED11") (class "Default")
      (node (ref "U5") (pin "2") (pinfunction "QC_2") (pintype "tri_state"))
      (node (ref "U7") (pin "3") (pinfunction "IN3_3") (pintype "input"))
    )
    (net (code "64") (name "/S_LED12") (class "Default")
      (node (ref "U5") (pin "3") (pinfunction "QD_3") (pintype "tri_state"))
      (node (ref "U7") (pin "4") (pinfunction "IN4_4") (pintype "input"))
    )
    (net (code "65") (name "/S_LED13") (class "Default")
      (node (ref "U5") (pin "4") (pinfunction "QE_4") (pintype "tri_state"))
      (node (ref "U7") (pin "5") (pinfunction "IN5_5") (pintype "input"))
    )
    (net (code "66") (name "/S_LED14") (class "Default")
      (node (ref "U5") (pin "5") (pinfunction "QF_5") (pintype "tri_state"))
      (node (ref "U7") (pin "6") (pinfunction "IN6_6") (pintype "input"))
    )
    (net (code "67") (name "/S_LED15") (class "Default")
      (node (ref "U5") (pin "6") (pinfunction "QG_6") (pintype "tri_state"))
      (node (ref "U7") (pin "7") (pinfunction "IN7_7") (pintype "input"))
    )
    (net (code "68") (name "/S_LED16") (class "Default")
      (node (ref "U5") (pin "7") (pinfunction "QH_7") (pintype "tri_state"))
      (node (ref "U7") (pin "8") (pinfunction "IN8_8") (pintype "input"))
    )
    (net (code "69") (name "/USART1_RX") (class "Default")
      (node (ref "MCU1") (pin "43") (pinfunction "PA10_43") (pintype "passive"))
      (node (ref "U3") (pin "1") (pinfunction "RO_1") (pintype "passive"))
    )
    (net (code "70") (name "/USART1_TX") (class "Default")
      (node (ref "MCU1") (pin "42") (pinfunction "PA9_42") (pintype "passive"))
      (node (ref "R33") (pin "1") (pinfunction "1_1") (pintype "passive"))
      (node (ref "R34") (pin "2") (pinfunction "2_2") (pintype "passive"))
      (node (ref "U3") (pin "4") (pinfunction "DI_4") (pintype "passive"))
    )
    (net (code "71") (name "/comm") (class "Default")
      (node (ref "MCU1") (pin "54") (pinfunction "PD2_54") (pintype "passive"))
      (node (ref "R57") (pin "2") (pinfunction "2_2") (pintype "passive"))
    )
    (net (code "72") (name "GND") (class "Default")
      (node (ref "C1") (pin "2") (pinfunction "2_2") (pintype "passive"))
      (node (ref "C10") (pin "1") (pinfunction "1_1") (pintype "passive"))
      (node (ref "C11") (pin "1") (pinfunction "1_1") (pintype "passive"))
      (node (ref "C12") (pin "2") (pinfunction "2_2") (pintype "passive"))
      (node (ref "C14") (pin "1") (pinfunction "1_1") (pintype "passive"))
      (node (ref "C15") (pin "1") (pinfunction "1_1") (pintype "passive"))
      (node (ref "C16") (pin "1") (pinfunction "1_1") (pintype "passive"))
      (node (ref "C17") (pin "1") (pinfunction "1_1") (pintype "passive"))
      (node (ref "C18") (pin "1") (pinfunction "1_1") (pintype "passive"))
      (node (ref "C19") (pin "1") (pinfunction "1_1") (pintype "passive"))
      (node (ref "C2") (pin "1") (pinfunction "1_1") (pintype "passive"))
      (node (ref "C20") (pin "1") (pinfunction "1_1") (pintype "passive"))
      (node (ref "C21") (pin "1") (pinfunction "1_1") (pintype "passive"))
      (node (ref "C22") (pin "2") (pinfunction "2_2") (pintype "passive"))
      (node (ref "C23") (pin "1") (pinfunction "1_1") (pintype "passive"))
      (node (ref "C24") (pin "2") (pinfunction "2_2") (pintype "passive"))
      (node (ref "C25") (pin "1") (pinfunction "1_1") (pintype "passive"))
      (node (ref "C26") (pin "1") (pinfunction "1_1") (pintype "passive"))
      (node (ref "C27") (pin "2") (pinfunction "2_2") (pintype "passive"))
      (node (ref "C3") (pin "1") (pinfunction "1_1") (pintype "passive"))
      (node (ref "C30") (pin "2") (pinfunction "2_2") (pintype "passive"))
      (node (ref "C31") (pin "1") (pinfunction "1_1") (pintype "passive"))
      (node (ref "C4") (pin "1") (pinfunction "1_1") (pintype "passive"))
      (node (ref "C5") (pin "1") (pinfunction "1_1") (pintype "passive"))
      (node (ref "C6") (pin "1") (pinfunction "1_1") (pintype "passive"))
      (node (ref "C7") (pin "1") (pinfunction "1_1") (pintype "passive"))
      (node (ref "C8") (pin "2") (pinfunction "2_2") (pintype "passive"))
      (node (ref "D2") (pin "1") (pinfunction "1_1") (pintype "passive"))
      (node (ref "LED1") (pin "K") (pinfunction "2_K") (pintype "passive"))
      (node (ref "LED2") (pin "K") (pinfunction "2_K") (pintype "passive"))
      (node (ref "MCU1") (pin "12") (pinfunction "VSSA_12") (pintype "passive"))
      (node (ref "MCU1") (pin "18") (pinfunction "VSS_18") (pintype "passive"))
      (node (ref "MCU1") (pin "31") (pinfunction "VSS_31") (pintype "passive"))
      (node (ref "MCU1") (pin "47") (pinfunction "VSS_47") (pintype "passive"))
      (node (ref "MCU1") (pin "63") (pinfunction "VSS_63") (pintype "passive"))
      (node (ref "P1") (pin "2") (pinfunction "2_2") (pintype "passive"))
      (node (ref "P2") (pin "19") (pinfunction "19_19") (pintype "passive"))
      (node (ref "P3") (pin "5") (pinfunction "5_5") (pintype "passive"))
      (node (ref "Q1") (pin "2") (pinfunction "2_2") (pintype "passive"))
      (node (ref "R1") (pin "2") (pinfunction "2_2") (pintype "passive"))
      (node (ref "R2") (pin "2") (pinfunction "2_2") (pintype "passive"))
      (node (ref "R24") (pin "2") (pinfunction "2_2") (pintype "passive"))
      (node (ref "R27") (pin "1") (pinfunction "1_1") (pintype "passive"))
      (node (ref "R29") (pin "2") (pinfunction "2_2") (pintype "passive"))
      (node (ref "R3") (pin "2") (pinfunction "2_2") (pintype "passive"))
      (node (ref "R30") (pin "2") (pinfunction "2_2") (pintype "passive"))
      (node (ref "R31") (pin "2") (pinfunction "2_2") (pintype "passive"))
      (node (ref "R4") (pin "1") (pinfunction "1_1") (pintype "passive"))
      (node (ref "R51") (pin "1") (pinfunction "1_1") (pintype "passive"))
      (node (ref "R54") (pin "2") (pinfunction "2_2") (pintype "passive"))
      (node (ref "R56") (pin "1") (pinfunction "1_1") (pintype "passive"))
      (node (ref "TVS1") (pin "1") (pinfunction "1_1") (pintype "passive"))
      (node (ref "U1") (pin "7") (pinfunction "GND_7") (pintype "passive"))
      (node (ref "U2") (pin "2") (pinfunction "GND_2") (pintype "passive"))
      (node (ref "U3") (pin "5") (pinfunction "GND_5") (pintype "passive"))
      (node (ref "U4") (pin "13") (pinfunction "~{OE}_13") (pintype "input"))
      (node (ref "U4") (pin "8") (pinfunction "GND_8") (pintype "power_in"))
      (node (ref "U5") (pin "13") (pinfunction "~{OE}_13") (pintype "input"))
      (node (ref "U5") (pin "8") (pinfunction "GND_8") (pintype "power_in"))
      (node (ref "U6") (pin "9") (pinfunction "GND_9") (pintype "passive"))
      (node (ref "U7") (pin "9") (pinfunction "GND_9") (pintype "passive"))
      (node (ref "US1") (pin "12") (pinfunction "MODE_12") (pintype "passive"))
      (node (ref "US1") (pin "19") (pinfunction "DVSS_19") (pintype "passive"))
      (node (ref "US1") (pin "5") (pinfunction "AVSS_5") (pintype "passive"))
      (node (ref "US2") (pin "12") (pinfunction "MODE_12") (pintype "passive"))
      (node (ref "US2") (pin "19") (pinfunction "DVSS_19") (pintype "passive"))
      (node (ref "US2") (pin "5") (pinfunction "AVSS_5") (pintype "passive"))
      (node (ref "US3") (pin "12") (pinfunction "MODE_12") (pintype "passive"))
      (node (ref "US3") (pin "19") (pinfunction "DVSS_19") (pintype "passive"))
      (node (ref "US3") (pin "5") (pinfunction "AVSS_5") (pintype "passive"))
      (node (ref "US4") (pin "12") (pinfunction "MODE_12") (pintype "passive"))
      (node (ref "US4") (pin "19") (pinfunction "DVSS_19") (pintype "passive"))
      (node (ref "US4") (pin "5") (pinfunction "AVSS_5") (pintype "passive"))
      (node (ref "US5") (pin "12") (pinfunction "MODE_12") (pintype "passive"))
      (node (ref "US5") (pin "19") (pinfunction "DVSS_19") (pintype "passive"))
      (node (ref "US5") (pin "5") (pinfunction "AVSS_5") (pintype "passive"))
      (node (ref "US6") (pin "12") (pinfunction "MODE_12") (pintype "passive"))
      (node (ref "US6") (pin "19") (pinfunction "DVSS_19") (pintype "passive"))
      (node (ref "US6") (pin "5") (pinfunction "AVSS_5") (pintype "passive"))
    )
    (net (code "73") (name "Net-(C10-Pad2)") (class "Default")
      (node (ref "C10") (pin "2") (pinfunction "2_2") (pintype "passive"))
      (node (ref "R23") (pin "1") (pinfunction "1_1") (pintype "passive"))
    )
    (net (code "74") (name "Net-(C12-Pad1)") (class "Default")
      (node (ref "C12") (pin "1") (pinfunction "1_1") (pintype "passive"))
      (node (ref "C31") (pin "2") (pinfunction "2_2") (pintype "passive"))
      (node (ref "L1") (pin "2") (pinfunction "2_2") (pintype "passive"))
      (node (ref "L2") (pin "1") (pinfunction "1_1") (pintype "passive"))
      (node (ref "R26") (pin "2") (pinfunction "2_2") (pintype "passive"))
    )
    (net (code "75") (name "Net-(LED1-1)") (class "Default")
      (node (ref "LED1") (pin "A") (pinfunction "1_A") (pintype "passive"))
      (node (ref "R28") (pin "1") (pinfunction "1_1") (pintype "passive"))
    )
    (net (code "76") (name "Net-(LED2-1)") (class "Default")
      (node (ref "LED2") (pin "A") (pinfunction "1_A") (pintype "passive"))
      (node (ref "R57") (pin "1") (pinfunction "1_1") (pintype "passive"))
    )
    (net (code "77") (name "Net-(LED3-2)") (class "Default")
      (node (ref "LED3") (pin "K") (pinfunction "2_K") (pintype "passive"))
      (node (ref "R59") (pin "2") (pinfunction "2_2") (pintype "passive"))
    )
    (net (code "78") (name "Net-(LED4-2)") (class "Default")
      (node (ref "LED4") (pin "K") (pinfunction "2_K") (pintype "passive"))
      (node (ref "R60") (pin "2") (pinfunction "2_2") (pintype "passive"))
    )
    (net (code "79") (name "Net-(LED5-2)") (class "Default")
      (node (ref "LED5") (pin "K") (pinfunction "2_K") (pintype "passive"))
      (node (ref "R61") (pin "2") (pinfunction "2_2") (pintype "passive"))
    )
    (net (code "80") (name "Net-(LED6-2)") (class "Default")
      (node (ref "LED6") (pin "K") (pinfunction "2_K") (pintype "passive"))
      (node (ref "R62") (pin "2") (pinfunction "2_2") (pintype "passive"))
    )
    (net (code "81") (name "Net-(LED7-2)") (class "Default")
      (node (ref "LED7") (pin "K") (pinfunction "2_K") (pintype "passive"))
      (node (ref "R63") (pin "2") (pinfunction "2_2") (pintype "passive"))
    )
    (net (code "82") (name "Net-(LED8-2)") (class "Default")
      (node (ref "LED8") (pin "K") (pinfunction "2_K") (pintype "passive"))
      (node (ref "R64") (pin "2") (pinfunction "2_2") (pintype "passive"))
    )
    (net (code "83") (name "Net-(LED9-2)") (class "Default")
      (node (ref "LED9") (pin "K") (pinfunction "2_K") (pintype "passive"))
      (node (ref "R65") (pin "2") (pinfunction "2_2") (pintype "passive"))
    )
    (net (code "84") (name "Net-(LED10-2)") (class "Default")
      (node (ref "LED10") (pin "K") (pinfunction "2_K") (pintype "passive"))
      (node (ref "R66") (pin "2") (pinfunction "2_2") (pintype "passive"))
    )
    (net (code "85") (name "Net-(LED11-2)") (class "Default")
      (node (ref "LED11") (pin "K") (pinfunction "2_K") (pintype "passive"))
      (node (ref "R67") (pin "2") (pinfunction "2_2") (pintype "passive"))
    )
    (net (code "86") (name "Net-(LED12-2)") (class "Default")
      (node (ref "LED12") (pin "K") (pinfunction "2_K") (pintype "passive"))
      (node (ref "R68") (pin "2") (pinfunction "2_2") (pintype "passive"))
    )
    (net (code "87") (name "Net-(LED13-2)") (class "Default")
      (node (ref "LED13") (pin "K") (pinfunction "2_K") (pintype "passive"))
      (node (ref "R69") (pin "2") (pinfunction "2_2") (pintype "passive"))
    )
    (net (code "88") (name "Net-(LED14-2)") (class "Default")
      (node (ref "LED14") (pin "K") (pinfunction "2_K") (pintype "passive"))
      (node (ref "R70") (pin "2") (pinfunction "2_2") (pintype "passive"))
    )
    (net (code "89") (name "Net-(LED15-2)") (class "Default")
      (node (ref "LED15") (pin "K") (pinfunction "2_K") (pintype "passive"))
      (node (ref "R71") (pin "2") (pinfunction "2_2") (pintype "passive"))
    )
    (net (code "90") (name "Net-(LED16-2)") (class "Default")
      (node (ref "LED16") (pin "K") (pinfunction "2_K") (pintype "passive"))
      (node (ref "R72") (pin "2") (pinfunction "2_2") (pintype "passive"))
    )
    (net (code "91") (name "Net-(LED17-2)") (class "Default")
      (node (ref "LED17") (pin "K") (pinfunction "2_K") (pintype "passive"))
      (node (ref "R73") (pin "2") (pinfunction "2_2") (pintype "passive"))
    )
    (net (code "92") (name "Net-(LED18-2)") (class "Default")
      (node (ref "LED18") (pin "K") (pinfunction "2_K") (pintype "passive"))
      (node (ref "R74") (pin "2") (pinfunction "2_2") (pintype "passive"))
    )
    (net (code "93") (name "Net-(MCU1-BOOT0)") (class "Default")
      (node (ref "MCU1") (pin "60") (pinfunction "BOOT0_60") (pintype "passive"))
      (node (ref "R54") (pin "1") (pinfunction "1_1") (pintype "passive"))
    )
    (net (code "94") (name "Net-(Q1-Pad1)") (class "Default")
      (node (ref "Q1") (pin "1") (pinfunction "1_1") (pintype "passive"))
      (node (ref "R33") (pin "2") (pinfunction "2_2") (pintype "passive"))
    )
    (net (code "95") (name "Net-(U1-BOOT)") (class "Default")
      (node (ref "C9") (pin "2") (pinfunction "2_2") (pintype "passive"))
      (node (ref "U1") (pin "1") (pinfunction "BOOT_1") (pintype "passive"))
    )
    (net (code "96") (name "Net-(U1-COMP)") (class "Default")
      (node (ref "C11") (pin "2") (pinfunction "2_2") (pintype "passive"))
      (node (ref "R23") (pin "2") (pinfunction "2_2") (pintype "passive"))
      (node (ref "U1") (pin "6") (pinfunction "COMP_6") (pintype "passive"))
    )
    (net (code "97") (name "Net-(U1-FB)") (class "Default")
      (node (ref "R26") (pin "1") (pinfunction "1_1") (pintype "passive"))
      (node (ref "R27") (pin "2") (pinfunction "2_2") (pintype "passive"))
      (node (ref "U1") (pin "5") (pinfunction "FB_5") (pintype "passive"))
    )
    (net (code "98") (name "Net-(U1-RT{slash}CLK)") (class "Default")
      (node (ref "R4") (pin "2") (pinfunction "2_2") (pintype "passive"))
      (node (ref "U1") (pin "4") (pinfunction "RT/CLK_4") (pintype "passive"))
    )
    (net (code "99") (name "Net-(U1-SW)") (class "Default")
      (node (ref "C9") (pin "1") (pinfunction "1_1") (pintype "passive"))
      (node (ref "D2") (pin "2") (pinfunction "2_2") (pintype "passive"))
      (node (ref "L1") (pin "1") (pinfunction "1_1") (pintype "passive"))
      (node (ref "U1") (pin "8") (pinfunction "SW_8") (pintype "passive"))
    )
    (net (code "100") (name "Net-(U1-VIN)") (class "Default")
      (node (ref "C1") (pin "1") (pinfunction "1_1") (pintype "passive"))
      (node (ref "D1") (pin "2") (pinfunction "2_2") (pintype "passive"))
      (node (ref "U1") (pin "2") (pinfunction "VIN_2") (pintype "passive"))
    )
    (net (code "101") (name "Net-(U2-RS)") (class "Default")
      (node (ref "R24") (pin "1") (pinfunction "1_1") (pintype "passive"))
      (node (ref "U2") (pin "8") (pinfunction "RS_8") (pintype "passive"))
    )
    (net (code "102") (name "Net-(U3-A)") (class "Default")
      (node (ref "R50") (pin "2") (pinfunction "2_2") (pintype "passive"))
      (node (ref "R52") (pin "2") (pinfunction "2_2") (pintype "passive"))
      (node (ref "U3") (pin "6") (pinfunction "A_6") (pintype "passive"))
    )
    (net (code "103") (name "Net-(U3-B)") (class "Default")
      (node (ref "R49") (pin "2") (pinfunction "2_2") (pintype "passive"))
      (node (ref "R51") (pin "2") (pinfunction "2_2") (pintype "passive"))
      (node (ref "U3") (pin "7") (pinfunction "B_7") (pintype "passive"))
    )
    (net (code "104") (name "Net-(U3-DE)") (class "Default")
      (node (ref "Q1") (pin "3") (pinfunction "3_3") (pintype "passive"))
      (node (ref "R32") (pin "2") (pinfunction "2_2") (pintype "passive"))
      (node (ref "U3") (pin "2") (pinfunction "~{RE}_2") (pintype "passive"))
      (node (ref "U3") (pin "3") (pinfunction "DE_3") (pintype "passive"))
    )
    (net (code "105") (name "Net-(U4-SDO)") (class "Default")
      (node (ref "U4") (pin "9") (pinfunction "SDO_9") (pintype "output"))
      (node (ref "U5") (pin "14") (pinfunction "SDI_14") (pintype "input"))
    )
    (net (code "106") (name "Net-(US1-REXT)") (class "Default")
      (node (ref "R3") (pin "1") (pinfunction "1_1") (pintype "passive"))
      (node (ref "US1") (pin "25") (pinfunction "REXT_25") (pintype "passive"))
    )
    (net (code "107") (name "Net-(US1-XDRVN)") (class "Default")
      (node (ref "R18") (pin "1") (pinfunction "1_1") (pintype "passive"))
      (node (ref "US1") (pin "18") (pinfunction "XDRVN_18") (pintype "passive"))
    )
    (net (code "108") (name "Net-(US1-XDRVR)") (class "Default")
      (node (ref "R17") (pin "1") (pinfunction "1_1") (pintype "passive"))
      (node (ref "US1") (pin "15") (pinfunction "XDRVR_15") (pintype "passive"))
    )
    (net (code "109") (name "Net-(US1-XINN)") (class "Default")
      (node (ref "R18") (pin "2") (pinfunction "2_2") (pintype "passive"))
      (node (ref "S3") (pin "1") (pinfunction "1_1") (pintype "passive"))
      (node (ref "US1") (pin "17") (pinfunction "XINN_17") (pintype "passive"))
    )
    (net (code "110") (name "Net-(US1-XINP)") (class "Default")
      (node (ref "R17") (pin "2") (pinfunction "2_2") (pintype "passive"))
      (node (ref "S3") (pin "2") (pinfunction "2_2") (pintype "passive"))
      (node (ref "US1") (pin "16") (pinfunction "XINP_16") (pintype "passive"))
    )
    (net (code "111") (name "Net-(US1-YDRVN)") (class "Default")
      (node (ref "R20") (pin "1") (pinfunction "1_1") (pintype "passive"))
      (node (ref "US1") (pin "14") (pinfunction "YDRVN_14") (pintype "passive"))
    )
    (net (code "112") (name "Net-(US1-YDRVR)") (class "Default")
      (node (ref "R19") (pin "1") (pinfunction "1_1") (pintype "passive"))
      (node (ref "US1") (pin "10") (pinfunction "YDRVR_10") (pintype "passive"))
    )
    (net (code "113") (name "Net-(US1-YINN)") (class "Default")
      (node (ref "R20") (pin "2") (pinfunction "2_2") (pintype "passive"))
      (node (ref "S2") (pin "1") (pinfunction "1_1") (pintype "passive"))
      (node (ref "US1") (pin "13") (pinfunction "YINN_13") (pintype "passive"))
    )
    (net (code "114") (name "Net-(US1-YINP)") (class "Default")
      (node (ref "R19") (pin "2") (pinfunction "2_2") (pintype "passive"))
      (node (ref "S2") (pin "2") (pinfunction "2_2") (pintype "passive"))
      (node (ref "US1") (pin "11") (pinfunction "YINP_11") (pintype "passive"))
    )
    (net (code "115") (name "Net-(US1-ZDRVN)") (class "Default")
      (node (ref "R22") (pin "1") (pinfunction "1_1") (pintype "passive"))
      (node (ref "US1") (pin "9") (pinfunction "ZDRVN_9") (pintype "passive"))
    )
    (net (code "116") (name "Net-(US1-ZDRVR)") (class "Default")
      (node (ref "R21") (pin "1") (pinfunction "1_1") (pintype "passive"))
      (node (ref "US1") (pin "6") (pinfunction "ZDRVR_6") (pintype "passive"))
    )
    (net (code "117") (name "Net-(US1-ZINN)") (class "Default")
      (node (ref "R22") (pin "2") (pinfunction "2_2") (pintype "passive"))
      (node (ref "S1") (pin "1") (pinfunction "1_1") (pintype "passive"))
      (node (ref "US1") (pin "8") (pinfunction "ZINN_8") (pintype "passive"))
    )
    (net (code "118") (name "Net-(US1-ZINP)") (class "Default")
      (node (ref "R21") (pin "2") (pinfunction "2_2") (pintype "passive"))
      (node (ref "S1") (pin "2") (pinfunction "2_2") (pintype "passive"))
      (node (ref "US1") (pin "7") (pinfunction "ZINP_7") (pintype "passive"))
    )
    (net (code "119") (name "Net-(US2-REXT)") (class "Default")
      (node (ref "R1") (pin "1") (pinfunction "1_1") (pintype "passive"))
      (node (ref "US2") (pin "25") (pinfunction "REXT_25") (pintype "passive"))
    )
    (net (code "120") (name "Net-(US2-XDRVN)") (class "Default")
      (node (ref "R6") (pin "1") (pinfunction "1_1") (pintype "passive"))
      (node (ref "US2") (pin "18") (pinfunction "XDRVN_18") (pintype "passive"))
    )
    (net (code "121") (name "Net-(US2-XDRVR)") (class "Default")
      (node (ref "R5") (pin "1") (pinfunction "1_1") (pintype "passive"))
      (node (ref "US2") (pin "15") (pinfunction "XDRVR_15") (pintype "passive"))
    )
    (net (code "122") (name "Net-(US2-XINN)") (class "Default")
      (node (ref "R6") (pin "2") (pinfunction "2_2") (pintype "passive"))
      (node (ref "S6") (pin "1") (pinfunction "1_1") (pintype "passive"))
      (node (ref "US2") (pin "17") (pinfunction "XINN_17") (pintype "passive"))
    )
    (net (code "123") (name "Net-(US2-XINP)") (class "Default")
      (node (ref "R5") (pin "2") (pinfunction "2_2") (pintype "passive"))
      (node (ref "S6") (pin "2") (pinfunction "2_2") (pintype "passive"))
      (node (ref "US2") (pin "16") (pinfunction "XINP_16") (pintype "passive"))
    )
    (net (code "124") (name "Net-(US2-YDRVN)") (class "Default")
      (node (ref "R8") (pin "1") (pinfunction "1_1") (pintype "passive"))
      (node (ref "US2") (pin "14") (pinfunction "YDRVN_14") (pintype "passive"))
    )
    (net (code "125") (name "Net-(US2-YDRVR)") (class "Default")
      (node (ref "R7") (pin "1") (pinfunction "1_1") (pintype "passive"))
      (node (ref "US2") (pin "10") (pinfunction "YDRVR_10") (pintype "passive"))
    )
    (net (code "126") (name "Net-(US2-YINN)") (class "Default")
      (node (ref "R8") (pin "2") (pinfunction "2_2") (pintype "passive"))
      (node (ref "S5") (pin "1") (pinfunction "1_1") (pintype "passive"))
      (node (ref "US2") (pin "13") (pinfunction "YINN_13") (pintype "passive"))
    )
    (net (code "127") (name "Net-(US2-YINP)") (class "Default")
      (node (ref "R7") (pin "2") (pinfunction "2_2") (pintype "passive"))
      (node (ref "S5") (pin "2") (pinfunction "2_2") (pintype "passive"))
      (node (ref "US2") (pin "11") (pinfunction "YINP_11") (pintype "passive"))
    )
    (net (code "128") (name "Net-(US2-ZDRVN)") (class "Default")
      (node (ref "R10") (pin "1") (pinfunction "1_1") (pintype "passive"))
      (node (ref "US2") (pin "9") (pinfunction "ZDRVN_9") (pintype "passive"))
    )
    (net (code "129") (name "Net-(US2-ZDRVR)") (class "Default")
      (node (ref "R9") (pin "1") (pinfunction "1_1") (pintype "passive"))
      (node (ref "US2") (pin "6") (pinfunction "ZDRVR_6") (pintype "passive"))
    )
    (net (code "130") (name "Net-(US2-ZINN)") (class "Default")
      (node (ref "R10") (pin "2") (pinfunction "2_2") (pintype "passive"))
      (node (ref "S4") (pin "1") (pinfunction "1_1") (pintype "passive"))
      (node (ref "US2") (pin "8") (pinfunction "ZINN_8") (pintype "passive"))
    )
    (net (code "131") (name "Net-(US2-ZINP)") (class "Default")
      (node (ref "R9") (pin "2") (pinfunction "2_2") (pintype "passive"))
      (node (ref "S4") (pin "2") (pinfunction "2_2") (pintype "passive"))
      (node (ref "US2") (pin "7") (pinfunction "ZINP_7") (pintype "passive"))
    )
    (net (code "132") (name "Net-(US3-REXT)") (class "Default")
      (node (ref "R2") (pin "1") (pinfunction "1_1") (pintype "passive"))
      (node (ref "US3") (pin "25") (pinfunction "REXT_25") (pintype "passive"))
    )
    (net (code "133") (name "Net-(US3-XDRVN)") (class "Default")
      (node (ref "R12") (pin "1") (pinfunction "1_1") (pintype "passive"))
      (node (ref "US3") (pin "18") (pinfunction "XDRVN_18") (pintype "passive"))
    )
    (net (code "134") (name "Net-(US3-XDRVR)") (class "Default")
      (node (ref "R11") (pin "1") (pinfunction "1_1") (pintype "passive"))
      (node (ref "US3") (pin "15") (pinfunction "XDRVR_15") (pintype "passive"))
    )
    (net (code "135") (name "Net-(US3-XINN)") (class "Default")
      (node (ref "R12") (pin "2") (pinfunction "2_2") (pintype "passive"))
      (node (ref "S9") (pin "1") (pinfunction "1_1") (pintype "passive"))
      (node (ref "US3") (pin "17") (pinfunction "XINN_17") (pintype "passive"))
    )
    (net (code "136") (name "Net-(US3-XINP)") (class "Default")
      (node (ref "R11") (pin "2") (pinfunction "2_2") (pintype "passive"))
      (node (ref "S9") (pin "2") (pinfunction "2_2") (pintype "passive"))
      (node (ref "US3") (pin "16") (pinfunction "XINP_16") (pintype "passive"))
    )
    (net (code "137") (name "Net-(US3-YDRVN)") (class "Default")
      (node (ref "R14") (pin "1") (pinfunction "1_1") (pintype "passive"))
      (node (ref "US3") (pin "14") (pinfunction "YDRVN_14") (pintype "passive"))
    )
    (net (code "138") (name "Net-(US3-YDRVR)") (class "Default")
      (node (ref "R13") (pin "1") (pinfunction "1_1") (pintype "passive"))
      (node (ref "US3") (pin "10") (pinfunction "YDRVR_10") (pintype "passive"))
    )
    (net (code "139") (name "Net-(US3-YINN)") (class "Default")
      (node (ref "R14") (pin "2") (pinfunction "2_2") (pintype "passive"))
      (node (ref "S8") (pin "1") (pinfunction "1_1") (pintype "passive"))
      (node (ref "US3") (pin "13") (pinfunction "YINN_13") (pintype "passive"))
    )
    (net (code "140") (name "Net-(US3-YINP)") (class "Default")
      (node (ref "R13") (pin "2") (pinfunction "2_2") (pintype "passive"))
      (node (ref "S8") (pin "2") (pinfunction "2_2") (pintype "passive"))
      (node (ref "US3") (pin "11") (pinfunction "YINP_11") (pintype "passive"))
    )
    (net (code "141") (name "Net-(US3-ZDRVN)") (class "Default")
      (node (ref "R16") (pin "1") (pinfunction "1_1") (pintype "passive"))
      (node (ref "US3") (pin "9") (pinfunction "ZDRVN_9") (pintype "passive"))
    )
    (net (code "142") (name "Net-(US3-ZDRVR)") (class "Default")
      (node (ref "R15") (pin "1") (pinfunction "1_1") (pintype "passive"))
      (node (ref "US3") (pin "6") (pinfunction "ZDRVR_6") (pintype "passive"))
    )
    (net (code "143") (name "Net-(US3-ZINN)") (class "Default")
      (node (ref "R16") (pin "2") (pinfunction "2_2") (pintype "passive"))
      (node (ref "S7") (pin "1") (pinfunction "1_1") (pintype "passive"))
      (node (ref "US3") (pin "8") (pinfunction "ZINN_8") (pintype "passive"))
    )
    (net (code "144") (name "Net-(US3-ZINP)") (class "Default")
      (node (ref "R15") (pin "2") (pinfunction "2_2") (pintype "passive"))
      (node (ref "S7") (pin "2") (pinfunction "2_2") (pintype "passive"))
      (node (ref "US3") (pin "7") (pinfunction "ZINP_7") (pintype "passive"))
    )
    (net (code "145") (name "Net-(US4-REXT)") (class "Default")
      (node (ref "R29") (pin "1") (pinfunction "1_1") (pintype "passive"))
      (node (ref "US4") (pin "25") (pinfunction "REXT_25") (pintype "passive"))
    )
    (net (code "146") (name "Net-(US4-XDRVN)") (class "Default")
      (node (ref "R36") (pin "1") (pinfunction "1_1") (pintype "passive"))
      (node (ref "US4") (pin "18") (pinfunction "XDRVN_18") (pintype "passive"))
    )
    (net (code "147") (name "Net-(US4-XDRVR)") (class "Default")
      (node (ref "R35") (pin "1") (pinfunction "1_1") (pintype "passive"))
      (node (ref "US4") (pin "15") (pinfunction "XDRVR_15") (pintype "passive"))
    )
    (net (code "148") (name "Net-(US4-XINN)") (class "Default")
      (node (ref "R36") (pin "2") (pinfunction "2_2") (pintype "passive"))
      (node (ref "S12") (pin "1") (pinfunction "1_1") (pintype "passive"))
      (node (ref "US4") (pin "17") (pinfunction "XINN_17") (pintype "passive"))
    )
    (net (code "149") (name "Net-(US4-XINP)") (class "Default")
      (node (ref "R35") (pin "2") (pinfunction "2_2") (pintype "passive"))
      (node (ref "S12") (pin "2") (pinfunction "2_2") (pintype "passive"))
      (node (ref "US4") (pin "16") (pinfunction "XINP_16") (pintype "passive"))
    )
    (net (code "150") (name "Net-(US4-YDRVN)") (class "Default")
      (node (ref "R38") (pin "1") (pinfunction "1_1") (pintype "passive"))
      (node (ref "US4") (pin "14") (pinfunction "YDRVN_14") (pintype "passive"))
    )
    (net (code "151") (name "Net-(US4-YDRVR)") (class "Default")
      (node (ref "R37") (pin "1") (pinfunction "1_1") (pintype "passive"))
      (node (ref "US4") (pin "10") (pinfunction "YDRVR_10") (pintype "passive"))
    )
    (net (code "152") (name "Net-(US4-YINN)") (class "Default")
      (node (ref "R38") (pin "2") (pinfunction "2_2") (pintype "passive"))
      (node (ref "S11") (pin "1") (pinfunction "1_1") (pintype "passive"))
      (node (ref "US4") (pin "13") (pinfunction "YINN_13") (pintype "passive"))
    )
    (net (code "153") (name "Net-(US4-YINP)") (class "Default")
      (node (ref "R37") (pin "2") (pinfunction "2_2") (pintype "passive"))
      (node (ref "S11") (pin "2") (pinfunction "2_2") (pintype "passive"))
      (node (ref "US4") (pin "11") (pinfunction "YINP_11") (pintype "passive"))
    )
    (net (code "154") (name "Net-(US4-ZDRVN)") (class "Default")
      (node (ref "R40") (pin "1") (pinfunction "1_1") (pintype "passive"))
      (node (ref "US4") (pin "9") (pinfunction "ZDRVN_9") (pintype "passive"))
    )
    (net (code "155") (name "Net-(US4-ZDRVR)") (class "Default")
      (node (ref "R39") (pin "1") (pinfunction "1_1") (pintype "passive"))
      (node (ref "US4") (pin "6") (pinfunction "ZDRVR_6") (pintype "passive"))
    )
    (net (code "156") (name "Net-(US4-ZINN)") (class "Default")
      (node (ref "R40") (pin "2") (pinfunction "2_2") (pintype "passive"))
      (node (ref "S10") (pin "1") (pinfunction "1_1") (pintype "passive"))
      (node (ref "US4") (pin "8") (pinfunction "ZINN_8") (pintype "passive"))
    )
    (net (code "157") (name "Net-(US4-ZINP)") (class "Default")
      (node (ref "R39") (pin "2") (pinfunction "2_2") (pintype "passive"))
      (node (ref "S10") (pin "2") (pinfunction "2_2") (pintype "passive"))
      (node (ref "US4") (pin "7") (pinfunction "ZINP_7") (pintype "passive"))
    )
    (net (code "158") (name "Net-(US5-REXT)") (class "Default")
      (node (ref "R30") (pin "1") (pinfunction "1_1") (pintype "passive"))
      (node (ref "US5") (pin "25") (pinfunction "REXT_25") (pintype "passive"))
    )
    (net (code "159") (name "Net-(US5-XDRVN)") (class "Default")
      (node (ref "R42") (pin "1") (pinfunction "1_1") (pintype "passive"))
      (node (ref "US5") (pin "18") (pinfunction "XDRVN_18") (pintype "passive"))
    )
    (net (code "160") (name "Net-(US5-XDRVR)") (class "Default")
      (node (ref "R41") (pin "1") (pinfunction "1_1") (pintype "passive"))
      (node (ref "US5") (pin "15") (pinfunction "XDRVR_15") (pintype "passive"))
    )
    (net (code "161") (name "Net-(US5-XINN)") (class "Default")
      (node (ref "R42") (pin "2") (pinfunction "2_2") (pintype "passive"))
      (node (ref "S15") (pin "1") (pinfunction "1_1") (pintype "passive"))
      (node (ref "US5") (pin "17") (pinfunction "XINN_17") (pintype "passive"))
    )
    (net (code "162") (name "Net-(US5-XINP)") (class "Default")
      (node (ref "R41") (pin "2") (pinfunction "2_2") (pintype "passive"))
      (node (ref "S15") (pin "2") (pinfunction "2_2") (pintype "passive"))
      (node (ref "US5") (pin "16") (pinfunction "XINP_16") (pintype "passive"))
    )
    (net (code "163") (name "Net-(US5-YDRVN)") (class "Default")
      (node (ref "R44") (pin "1") (pinfunction "1_1") (pintype "passive"))
      (node (ref "US5") (pin "14") (pinfunction "YDRVN_14") (pintype "passive"))
    )
    (net (code "164") (name "Net-(US5-YDRVR)") (class "Default")
      (node (ref "R43") (pin "1") (pinfunction "1_1") (pintype "passive"))
      (node (ref "US5") (pin "10") (pinfunction "YDRVR_10") (pintype "passive"))
    )
    (net (code "165") (name "Net-(US5-YINN)") (class "Default")
      (node (ref "R44") (pin "2") (pinfunction "2_2") (pintype "passive"))
      (node (ref "S14") (pin "1") (pinfunction "1_1") (pintype "passive"))
      (node (ref "US5") (pin "13") (pinfunction "YINN_13") (pintype "passive"))
    )
    (net (code "166") (name "Net-(US5-YINP)") (class "Default")
      (node (ref "R43") (pin "2") (pinfunction "2_2") (pintype "passive"))
      (node (ref "S14") (pin "2") (pinfunction "2_2") (pintype "passive"))
      (node (ref "US5") (pin "11") (pinfunction "YINP_11") (pintype "passive"))
    )
    (net (code "167") (name "Net-(US5-ZDRVN)") (class "Default")
      (node (ref "R46") (pin "1") (pinfunction "1_1") (pintype "passive"))
      (node (ref "US5") (pin "9") (pinfunction "ZDRVN_9") (pintype "passive"))
    )
    (net (code "168") (name "Net-(US5-ZDRVR)") (class "Default")
      (node (ref "R45") (pin "1") (pinfunction "1_1") (pintype "passive"))
      (node (ref "US5") (pin "6") (pinfunction "ZDRVR_6") (pintype "passive"))
    )
    (net (code "169") (name "Net-(US5-ZINN)") (class "Default")
      (node (ref "R46") (pin "2") (pinfunction "2_2") (pintype "passive"))
      (node (ref "S13") (pin "1") (pinfunction "1_1") (pintype "passive"))
      (node (ref "US5") (pin "8") (pinfunction "ZINN_8") (pintype "passive"))
    )
    (net (code "170") (name "Net-(US5-ZINP)") (class "Default")
      (node (ref "R45") (pin "2") (pinfunction "2_2") (pintype "passive"))
      (node (ref "S13") (pin "2") (pinfunction "2_2") (pintype "passive"))
      (node (ref "US5") (pin "7") (pinfunction "ZINP_7") (pintype "passive"))
    )
    (net (code "171") (name "Net-(US6-REXT)") (class "Default")
      (node (ref "R31") (pin "1") (pinfunction "1_1") (pintype "passive"))
      (node (ref "US6") (pin "25") (pinfunction "REXT_25") (pintype "passive"))
    )
    (net (code "172") (name "Net-(US6-ZDRVN)") (class "Default")
      (node (ref "R48") (pin "1") (pinfunction "1_1") (pintype "passive"))
      (node (ref "US6") (pin "9") (pinfunction "ZDRVN_9") (pintype "passive"))
    )
    (net (code "173") (name "Net-(US6-ZDRVR)") (class "Default")
      (node (ref "R47") (pin "1") (pinfunction "1_1") (pintype "passive"))
      (node (ref "US6") (pin "6") (pinfunction "ZDRVR_6") (pintype "passive"))
    )
    (net (code "174") (name "Net-(US6-ZINN)") (class "Default")
      (node (ref "R48") (pin "2") (pinfunction "2_2") (pintype "passive"))
      (node (ref "S16") (pin "1") (pinfunction "1_1") (pintype "passive"))
      (node (ref "US6") (pin "8") (pinfunction "ZINN_8") (pintype "passive"))
    )
    (net (code "175") (name "Net-(US6-ZINP)") (class "Default")
      (node (ref "R47") (pin "2") (pinfunction "2_2") (pintype "passive"))
      (node (ref "S16") (pin "2") (pinfunction "2_2") (pintype "passive"))
      (node (ref "US6") (pin "7") (pinfunction "ZINP_7") (pintype "passive"))
    )
    (net (code "176") (name "VCC3.3V") (class "Default")
      (node (ref "C14") (pin "2") (pinfunction "2_2") (pintype "passive"))
      (node (ref "C15") (pin "2") (pinfunction "2_2") (pintype "passive"))
      (node (ref "C16") (pin "2") (pinfunction "2_2") (pintype "passive"))
      (node (ref "C17") (pin "2") (pinfunction "2_2") (pintype "passive"))
      (node (ref "C18") (pin "2") (pinfunction "2_2") (pintype "passive"))
      (node (ref "C19") (pin "2") (pinfunction "2_2") (pintype "passive"))
      (node (ref "C2") (pin "2") (pinfunction "2_2") (pintype "passive"))
      (node (ref "C22") (pin "1") (pinfunction "1_1") (pintype "passive"))
      (node (ref "C24") (pin "1") (pinfunction "1_1") (pintype "passive"))
      (node (ref "C25") (pin "2") (pinfunction "2_2") (pintype "passive"))
      (node (ref "C26") (pin "2") (pinfunction "2_2") (pintype "passive"))
      (node (ref "C27") (pin "1") (pinfunction "1_1") (pintype "passive"))
      (node (ref "C3") (pin "2") (pinfunction "2_2") (pintype "passive"))
      (node (ref "C30") (pin "1") (pinfunction "1_1") (pintype "passive"))
      (node (ref "C4") (pin "2") (pinfunction "2_2") (pintype "passive"))
      (node (ref "C5") (pin "2") (pinfunction "2_2") (pintype "passive"))
      (node (ref "C6") (pin "2") (pinfunction "2_2") (pintype "passive"))
      (node (ref "C7") (pin "2") (pinfunction "2_2") (pintype "passive"))
      (node (ref "C8") (pin "1") (pinfunction "1_1") (pintype "passive"))
      (node (ref "L2") (pin "2") (pinfunction "2_2") (pintype "passive"))
      (node (ref "MCU1") (pin "13") (pinfunction "VDDA_13") (pintype "passive"))
      (node (ref "MCU1") (pin "19") (pinfunction "VDD_19") (pintype "passive"))
      (node (ref "MCU1") (pin "32") (pinfunction "VDD_32") (pintype "passive"))
      (node (ref "MCU1") (pin "48") (pinfunction "VDD_48") (pintype "passive"))
      (node (ref "MCU1") (pin "64") (pinfunction "VDD_64") (pintype "passive"))
      (node (ref "P3") (pin "1") (pinfunction "1_1") (pintype "passive"))
      (node (ref "R28") (pin "2") (pinfunction "2_2") (pintype "passive"))
      (node (ref "R32") (pin "1") (pinfunction "1_1") (pintype "passive"))
      (node (ref "R34") (pin "1") (pinfunction "1_1") (pintype "passive"))
      (node (ref "R52") (pin "1") (pinfunction "1_1") (pintype "passive"))
      (node (ref "R53") (pin "2") (pinfunction "2_2") (pintype "passive"))
      (node (ref "R55") (pin "1") (pinfunction "1_1") (pintype "passive"))
      (node (ref "R58") (pin "1") (pinfunction "1_1") (pintype "passive"))
      (node (ref "TVS1") (pin "2") (pinfunction "2_2") (pintype "passive"))
      (node (ref "U2") (pin "3") (pinfunction "VCC_3") (pintype "passive"))
      (node (ref "U3") (pin "8") (pinfunction "VCC_8") (pintype "passive"))
      (node (ref "U4") (pin "10") (pinfunction "~{RST}_10") (pintype "input"))
      (node (ref "U4") (pin "16") (pinfunction "VDD_16") (pintype "power_in"))
      (node (ref "U5") (pin "10") (pinfunction "~{RST}_10") (pintype "input"))
      (node (ref "U5") (pin "16") (pinfunction "VDD_16") (pintype "power_in"))
      (node (ref "US1") (pin "26") (pinfunction "DVDD_26") (pintype "passive"))
      (node (ref "US1") (pin "4") (pinfunction "AVDD_4") (pintype "passive"))
      (node (ref "US2") (pin "26") (pinfunction "DVDD_26") (pintype "passive"))
      (node (ref "US2") (pin "4") (pinfunction "AVDD_4") (pintype "passive"))
      (node (ref "US3") (pin "26") (pinfunction "DVDD_26") (pintype "passive"))
      (node (ref "US3") (pin "4") (pinfunction "AVDD_4") (pintype "passive"))
      (node (ref "US4") (pin "26") (pinfunction "DVDD_26") (pintype "passive"))
      (node (ref "US4") (pin "4") (pinfunction "AVDD_4") (pintype "passive"))
      (node (ref "US5") (pin "26") (pinfunction "DVDD_26") (pintype "passive"))
      (node (ref "US5") (pin "4") (pinfunction "AVDD_4") (pintype "passive"))
      (node (ref "US6") (pin "26") (pinfunction "DVDD_26") (pintype "passive"))
      (node (ref "US6") (pin "4") (pinfunction "AVDD_4") (pintype "passive"))
    )
    (net (code "177") (name "VCC_IN") (class "Default")
      (node (ref "D1") (pin "1") (pinfunction "1_1") (pintype "passive"))
      (node (ref "LED10") (pin "A") (pinfunction "1_A") (pintype "passive"))
      (node (ref "LED11") (pin "A") (pinfunction "1_A") (pintype "passive"))
      (node (ref "LED12") (pin "A") (pinfunction "1_A") (pintype "passive"))
      (node (ref "LED13") (pin "A") (pinfunction "1_A") (pintype "passive"))
      (node (ref "LED14") (pin "A") (pinfunction "1_A") (pintype "passive"))
      (node (ref "LED15") (pin "A") (pinfunction "1_A") (pintype "passive"))
      (node (ref "LED16") (pin "A") (pinfunction "1_A") (pintype "passive"))
      (node (ref "LED17") (pin "A") (pinfunction "1_A") (pintype "passive"))
      (node (ref "LED18") (pin "A") (pinfunction "1_A") (pintype "passive"))
      (node (ref "LED3") (pin "A") (pinfunction "1_A") (pintype "passive"))
      (node (ref "LED4") (pin "A") (pinfunction "1_A") (pintype "passive"))
      (node (ref "LED5") (pin "A") (pinfunction "1_A") (pintype "passive"))
      (node (ref "LED6") (pin "A") (pinfunction "1_A") (pintype "passive"))
      (node (ref "LED7") (pin "A") (pinfunction "1_A") (pintype "passive"))
      (node (ref "LED8") (pin "A") (pinfunction "1_A") (pintype "passive"))
      (node (ref "LED9") (pin "A") (pinfunction "1_A") (pintype "passive"))
      (node (ref "P1") (pin "1") (pinfunction "1_1") (pintype "passive"))
      (node (ref "P2") (pin "20") (pinfunction "20_20") (pintype "passive"))
    )
    (net (code "178") (name "unconnected-(MCU1-PA3-Pad17)") (class "Default")
      (node (ref "MCU1") (pin "17") (pinfunction "PA3_17") (pintype "passive"))
    )
    (net (code "179") (name "unconnected-(MCU1-PA4-Pad20)") (class "Default")
      (node (ref "MCU1") (pin "20") (pinfunction "PA4_20") (pintype "passive"))
    )
    (net (code "180") (name "unconnected-(MCU1-PA8-Pad41)") (class "Default")
      (node (ref "MCU1") (pin "41") (pinfunction "PA8_41") (pintype "passive"))
    )
    (net (code "181") (name "unconnected-(MCU1-PA15{slash}JTDI-Pad50)") (class "Default")
      (node (ref "MCU1") (pin "50") (pinfunction "PA15/JTDI_50") (pintype "passive"))
    )
    (net (code "182") (name "unconnected-(MCU1-PB3{slash}JTDO-Pad55)") (class "Default")
      (node (ref "MCU1") (pin "55") (pinfunction "PB3/JTDO_55") (pintype "passive"))
    )
    (net (code "183") (name "unconnected-(MCU1-PB5-Pad57)") (class "Default")
      (node (ref "MCU1") (pin "57") (pinfunction "PB5_57") (pintype "passive"))
    )
    (net (code "184") (name "unconnected-(MCU1-PB6-Pad58)") (class "Default")
      (node (ref "MCU1") (pin "58") (pinfunction "PB6_58") (pintype "passive"))
    )
    (net (code "185") (name "unconnected-(MCU1-PB7-Pad59)") (class "Default")
      (node (ref "MCU1") (pin "59") (pinfunction "PB7_59") (pintype "passive"))
    )
    (net (code "186") (name "unconnected-(MCU1-PB8-Pad61)") (class "Default")
      (node (ref "MCU1") (pin "61") (pinfunction "PB8_61") (pintype "passive"))
    )
    (net (code "187") (name "unconnected-(MCU1-PB9-Pad62)") (class "Default")
      (node (ref "MCU1") (pin "62") (pinfunction "PB9_62") (pintype "passive"))
    )
    (net (code "188") (name "unconnected-(MCU1-PC0-Pad8)") (class "Default")
      (node (ref "MCU1") (pin "8") (pinfunction "PC0_8") (pintype "passive"))
    )
    (net (code "189") (name "unconnected-(MCU1-PC1-Pad9)") (class "Default")
      (node (ref "MCU1") (pin "9") (pinfunction "PC1_9") (pintype "passive"))
    )
    (net (code "190") (name "unconnected-(MCU1-PC2-Pad10)") (class "Default")
      (node (ref "MCU1") (pin "10") (pinfunction "PC2_10") (pintype "passive"))
    )
    (net (code "191") (name "unconnected-(MCU1-PC3-Pad11)") (class "Default")
      (node (ref "MCU1") (pin "11") (pinfunction "PC3_11") (pintype "passive"))
    )
    (net (code "192") (name "unconnected-(MCU1-PC13-ANTI_TAMP-Pad2)") (class "Default")
      (node (ref "MCU1") (pin "2") (pinfunction "PC13-ANTI_TAMP_2") (pintype "passive"))
    )
    (net (code "193") (name "unconnected-(MCU1-PC14-OSC32_IN-Pad3)") (class "Default")
      (node (ref "MCU1") (pin "3") (pinfunction "PC14-OSC32_IN_3") (pintype "passive"))
    )
    (net (code "194") (name "unconnected-(MCU1-PC15-OSC32_OUT-Pad4)") (class "Default")
      (node (ref "MCU1") (pin "4") (pinfunction "PC15-OSC32_OUT_4") (pintype "passive"))
    )
    (net (code "195") (name "unconnected-(MCU1-VBAT-Pad1)") (class "Default")
      (node (ref "MCU1") (pin "1") (pinfunction "VBAT_1") (pintype "passive"))
    )
    (net (code "196") (name "unconnected-(P2-Pad17)") (class "Default")
      (node (ref "P2") (pin "17") (pinfunction "17_17") (pintype "passive"))
    )
    (net (code "197") (name "unconnected-(P2-Pad18)") (class "Default")
      (node (ref "P2") (pin "18") (pinfunction "18_18") (pintype "passive"))
    )
    (net (code "198") (name "unconnected-(U1-EN-Pad3)") (class "Default")
      (node (ref "U1") (pin "3") (pinfunction "EN_3") (pintype "passive"))
    )
    (net (code "199") (name "unconnected-(U2-Vref-Pad5)") (class "Default")
      (node (ref "U2") (pin "5") (pinfunction "Vref_5") (pintype "passive"))
    )
    (net (code "200") (name "unconnected-(U5-SDO-Pad9)") (class "Default")
      (node (ref "U5") (pin "9") (pinfunction "SDO_9") (pintype "output"))
    )
    (net (code "201") (name "unconnected-(U6-COM-Pad10)") (class "Default")
      (node (ref "U6") (pin "10") (pinfunction "COM_10") (pintype "power_in"))
    )
    (net (code "202") (name "unconnected-(U7-COM-Pad10)") (class "Default")
      (node (ref "U7") (pin "10") (pinfunction "COM_10") (pintype "power_in"))
    )
    (net (code "203") (name "unconnected-(US6-XDRVN-Pad18)") (class "Default")
      (node (ref "US6") (pin "18") (pinfunction "XDRVN_18") (pintype "passive"))
    )
    (net (code "204") (name "unconnected-(US6-XDRVR-Pad15)") (class "Default")
      (node (ref "US6") (pin "15") (pinfunction "XDRVR_15") (pintype "passive"))
    )
    (net (code "205") (name "unconnected-(US6-XINN-Pad17)") (class "Default")
      (node (ref "US6") (pin "17") (pinfunction "XINN_17") (pintype "passive"))
    )
    (net (code "206") (name "unconnected-(US6-XINP-Pad16)") (class "Default")
      (node (ref "US6") (pin "16") (pinfunction "XINP_16") (pintype "passive"))
    )
    (net (code "207") (name "unconnected-(US6-YDRVN-Pad14)") (class "Default")
      (node (ref "US6") (pin "14") (pinfunction "YDRVN_14") (pintype "passive"))
    )
    (net (code "208") (name "unconnected-(US6-YDRVR-Pad10)") (class "Default")
      (node (ref "US6") (pin "10") (pinfunction "YDRVR_10") (pintype "passive"))
    )
    (net (code "209") (name "unconnected-(US6-YINN-Pad13)") (class "Default")
      (node (ref "US6") (pin "13") (pinfunction "YINN_13") (pintype "passive"))
    )
    (net (code "210") (name "unconnected-(US6-YINP-Pad11)") (class "Default")
      (node (ref "US6") (pin "11") (pinfunction "YINP_11") (pintype "passive"))
    )
  )
)
